# Matias_OBC-v_3_0.net
KiCad netlist of a schematic drawn in EAGLE
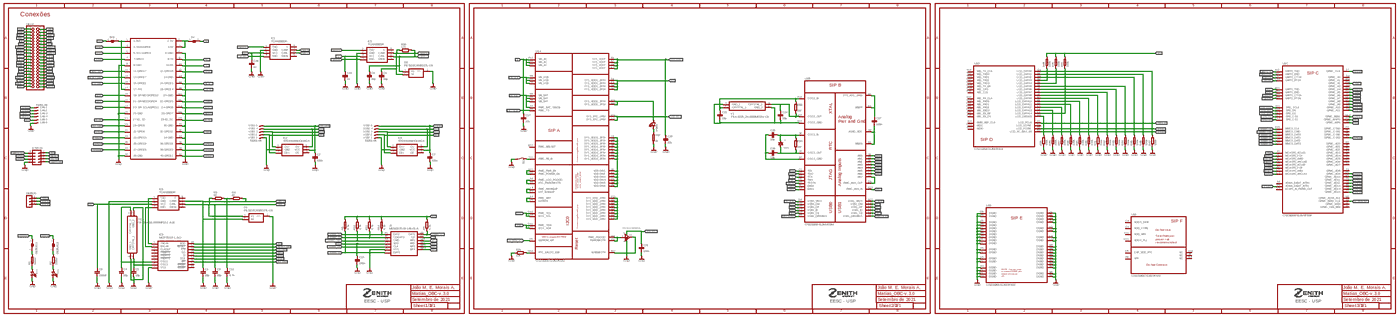
[diagram p0: schematic, sheet 1, overview]
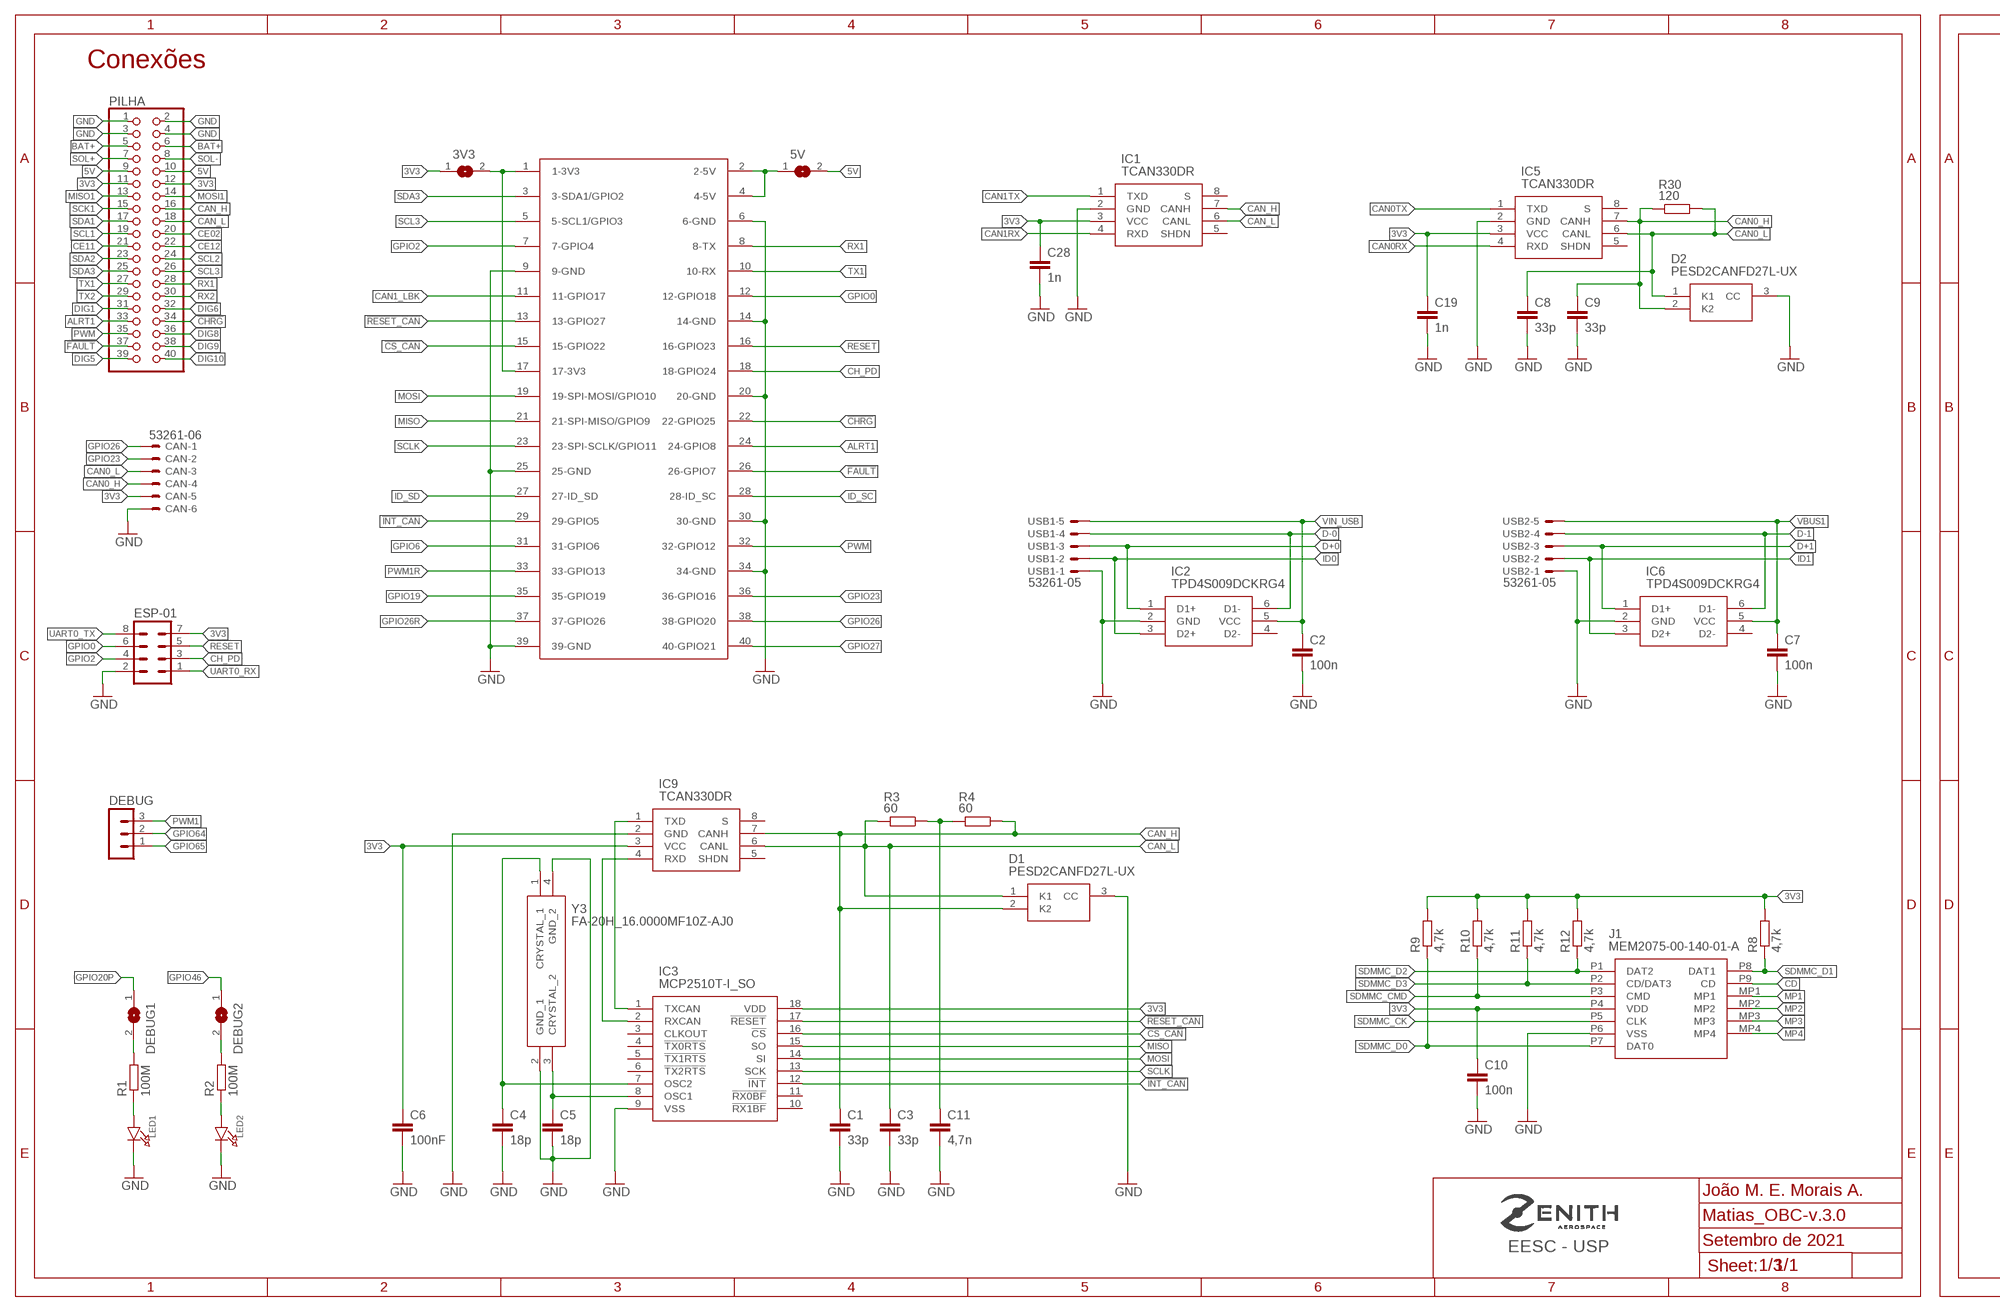
[diagram p1: schematic, sheet 1, part 1 of 4]
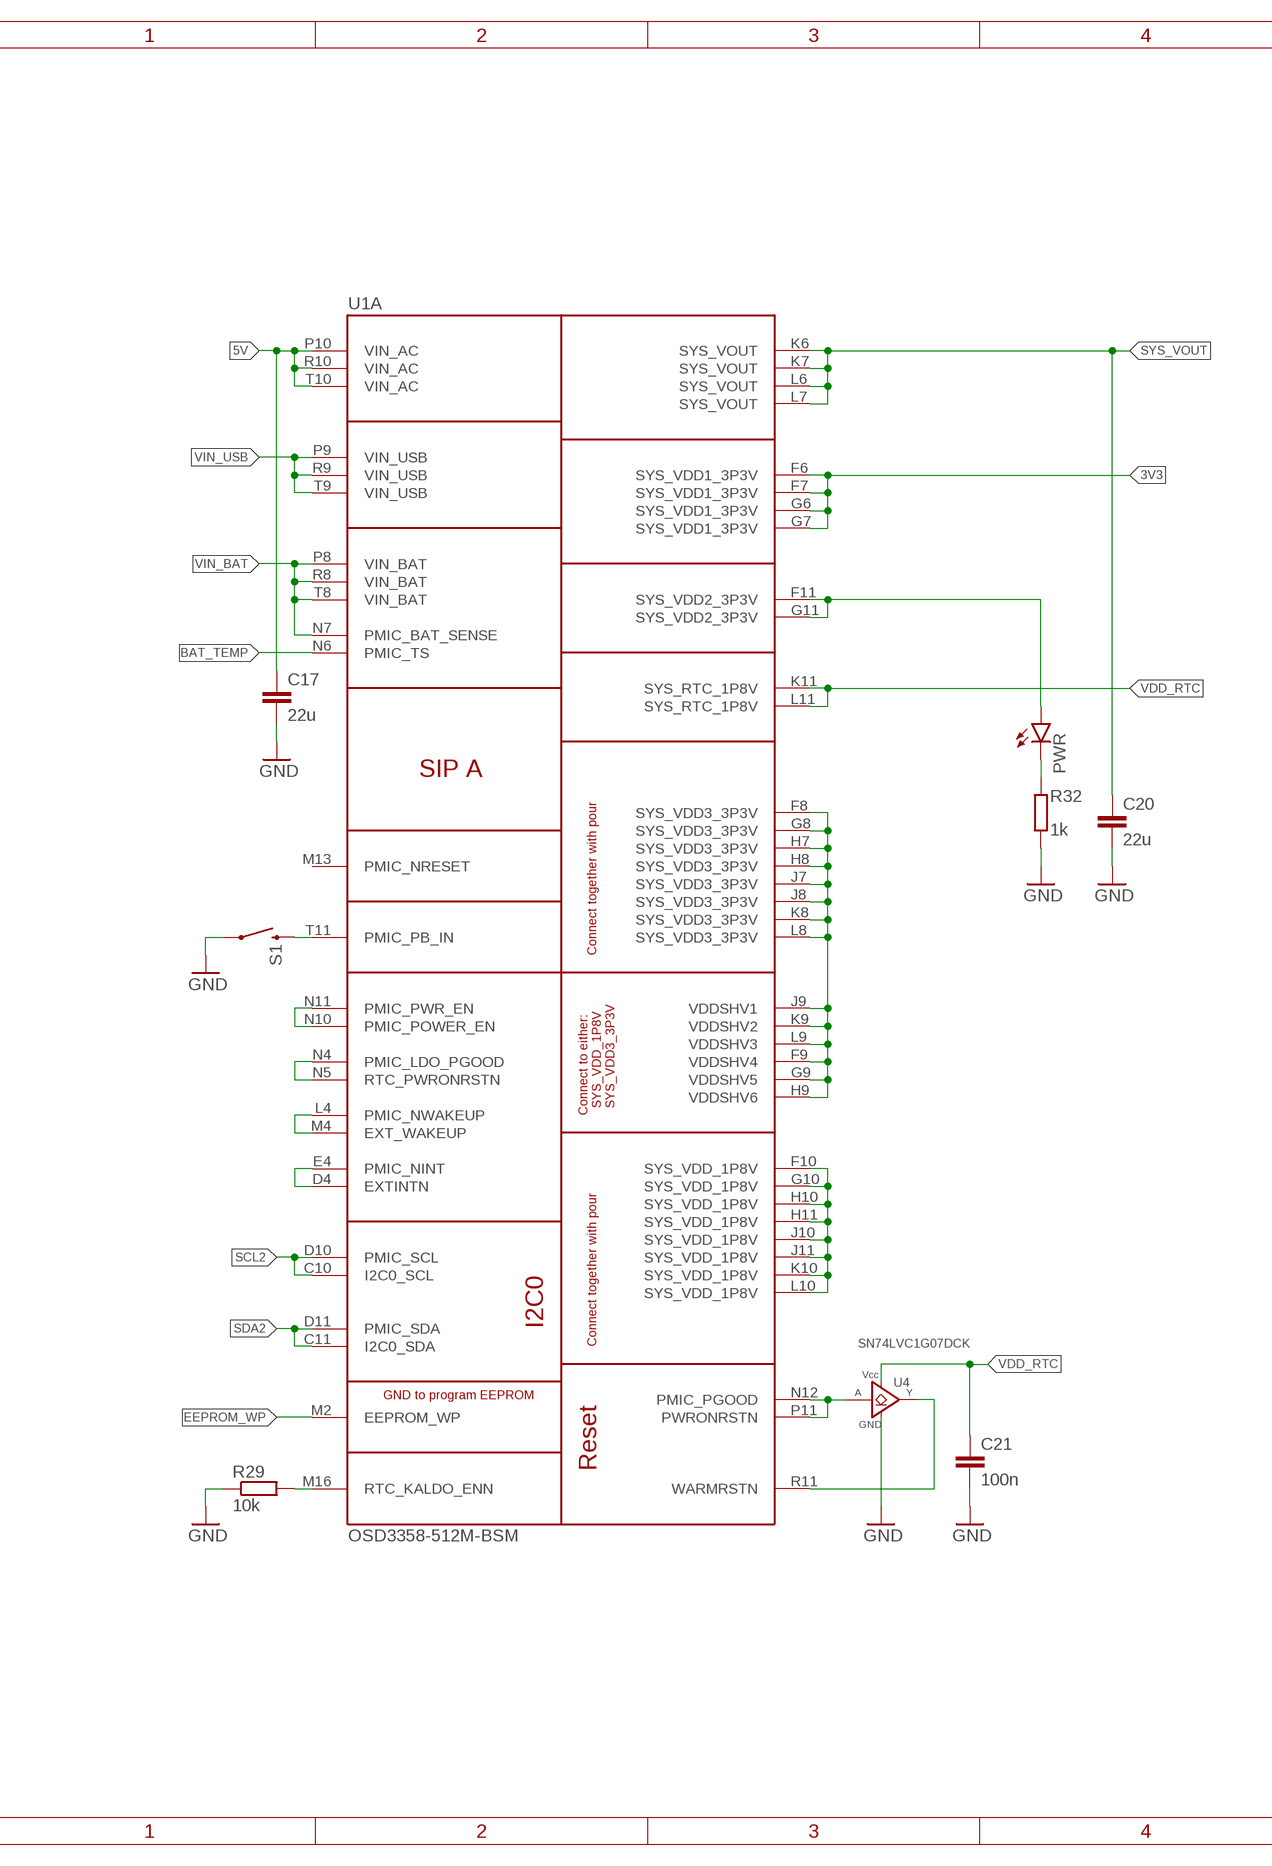
[diagram p2: schematic, sheet 1, part 2 of 4]
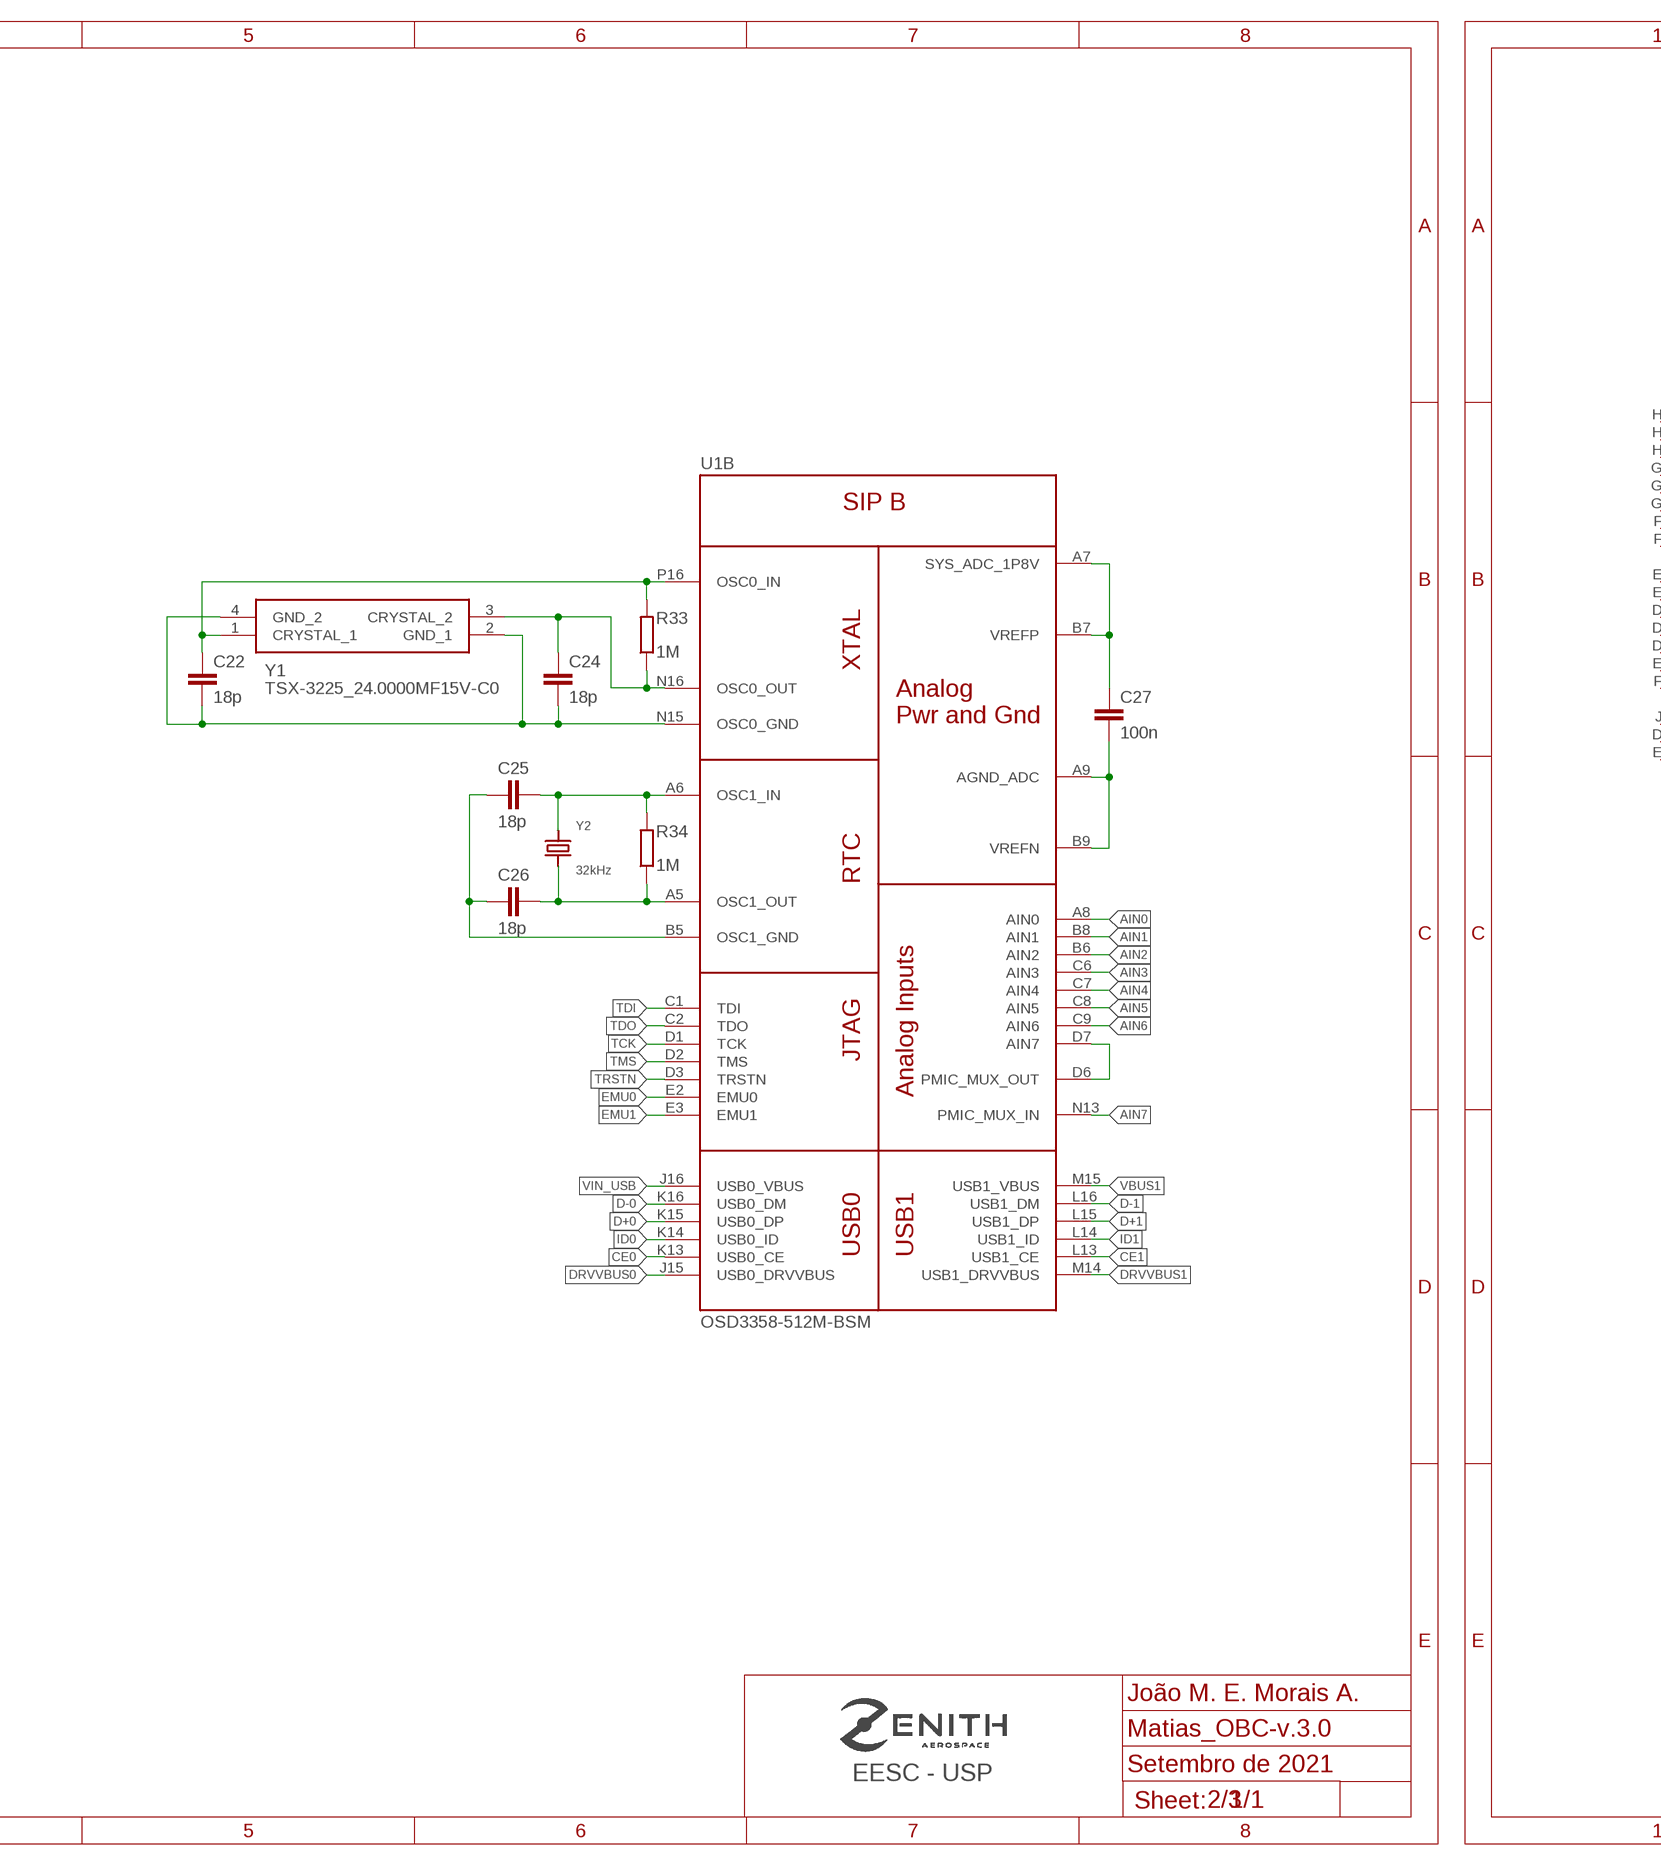
[diagram p3: schematic, sheet 1, part 3 of 4]
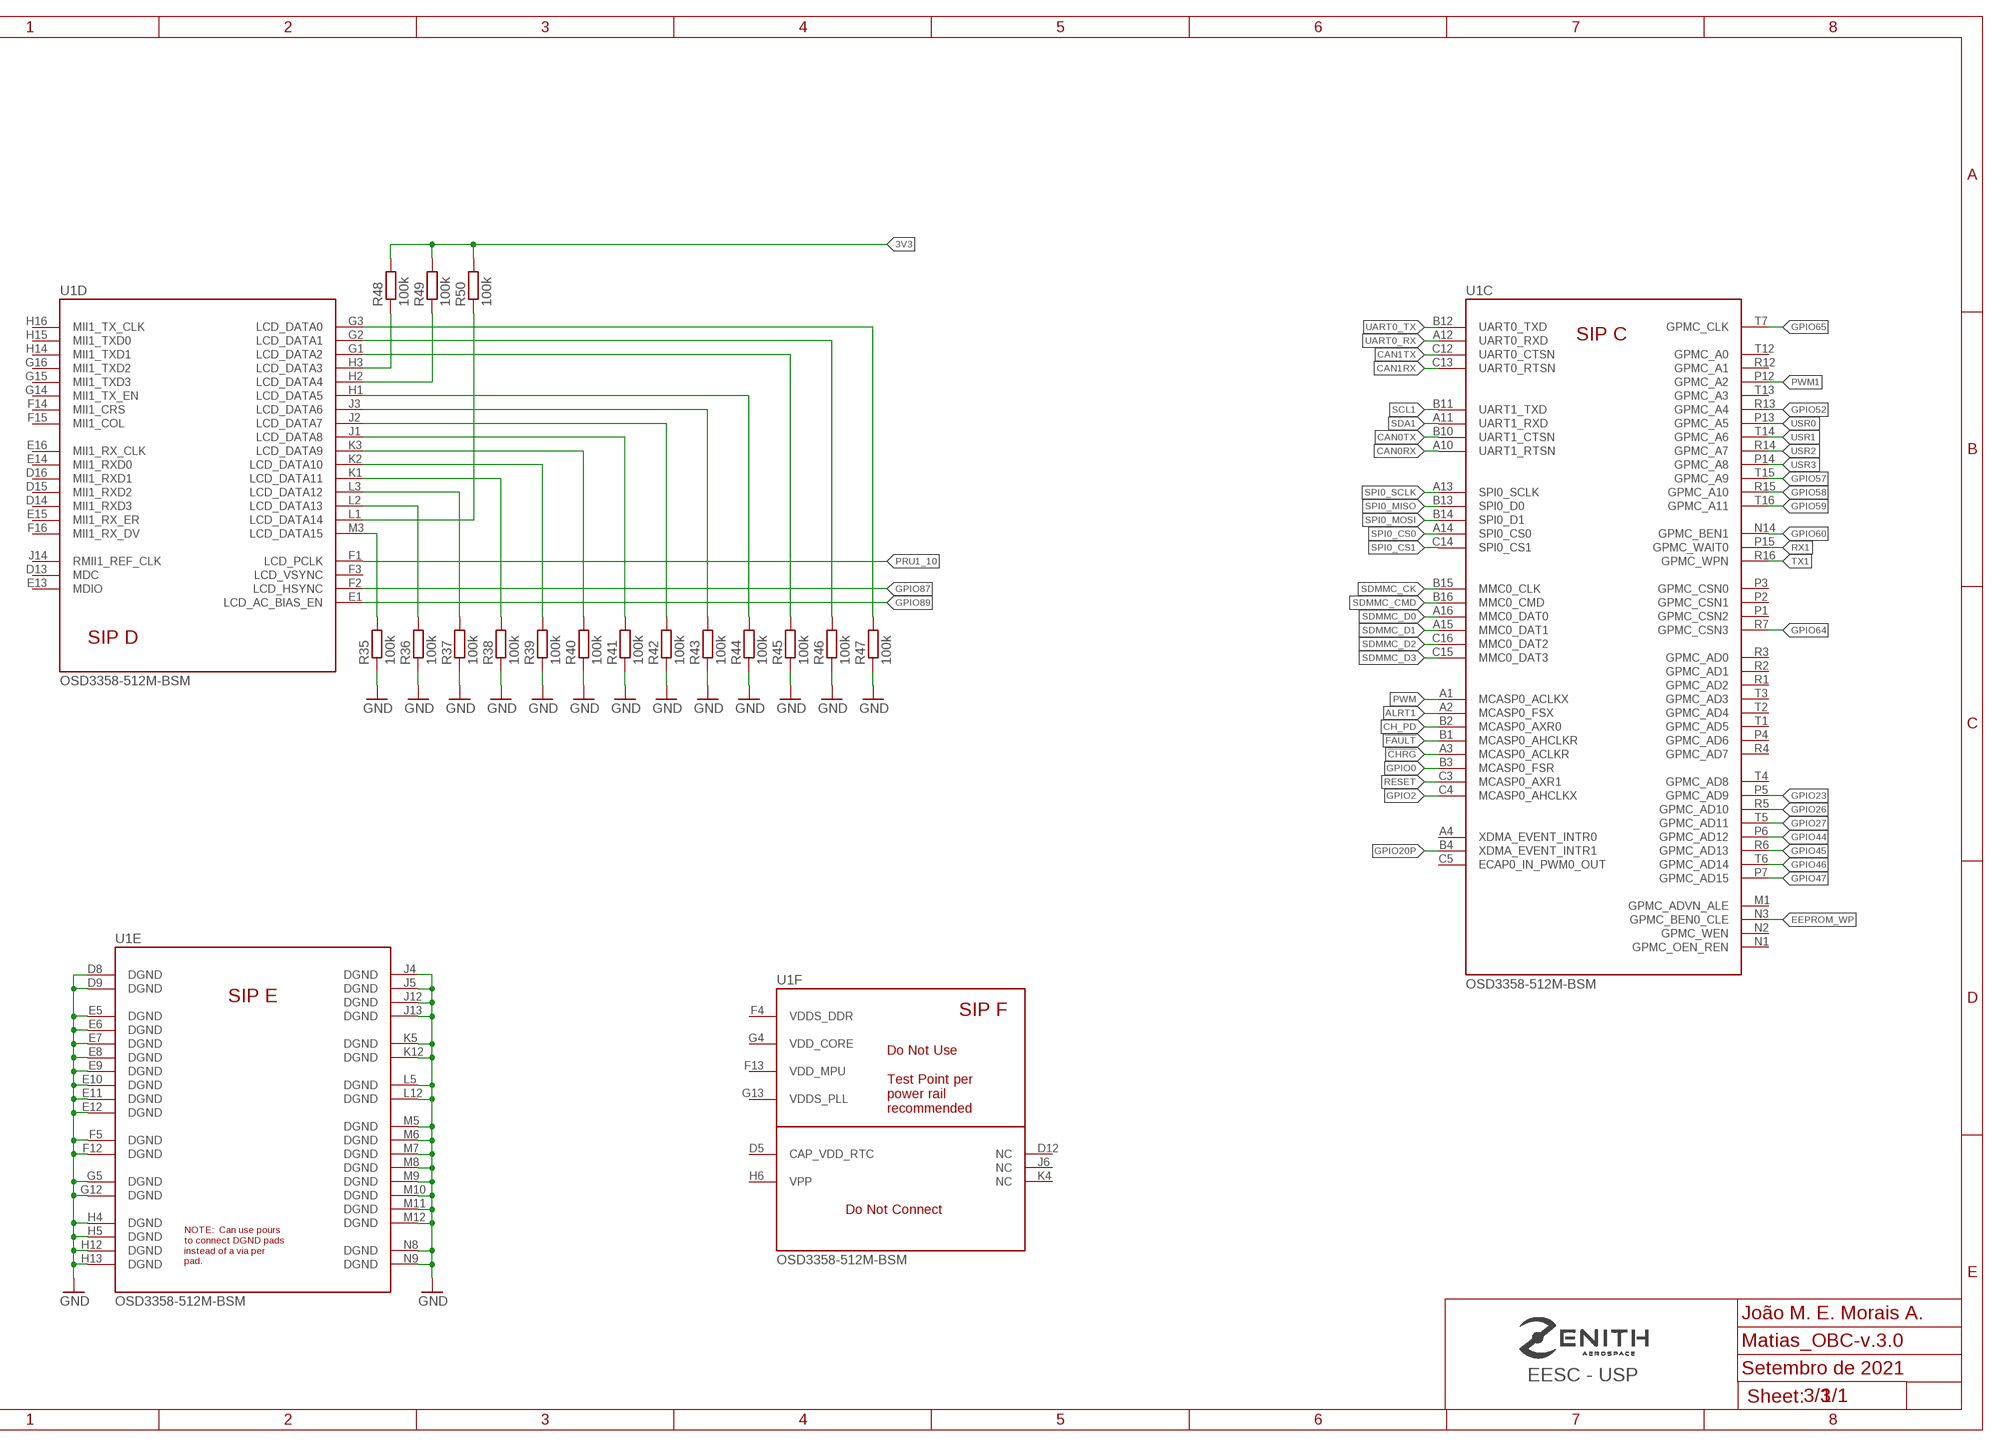
[diagram p4: schematic, sheet 1, part 4 of 4]

(export (version "E")
  (design (tool "Eeschema 10.0.6"))
  (components
    (comp (ref "3V3") (value "SJ") (footprint "eagle-import:SJ") (libsource (lib "eagle-import") (part "SJ")))
    (comp (ref "5V") (value "SJ") (footprint "eagle-import:SJ") (libsource (lib "eagle-import") (part "SJ")))
    (comp (ref "C1")
      (value "33p")
      (footprint "eagle-import:C0805")
      (libsource (lib "eagle-import") (part "C-EUC0805"))
    )
    (comp (ref "C2")
      (value "100n")
      (footprint "eagle-import:C0805")
      (libsource (lib "eagle-import") (part "C-EUC0805"))
    )
    (comp (ref "C3")
      (value "33p")
      (footprint "eagle-import:C0805")
      (libsource (lib "eagle-import") (part "C-EUC0805"))
    )
    (comp (ref "C4")
      (value "18p")
      (footprint "eagle-import:C0805")
      (libsource (lib "eagle-import") (part "C-EUC0805"))
    )
    (comp (ref "C5")
      (value "18p")
      (footprint "eagle-import:C0805")
      (libsource (lib "eagle-import") (part "C-EUC0805"))
    )
    (comp (ref "C6")
      (value "100nF")
      (footprint "eagle-import:C0805")
      (libsource (lib "eagle-import") (part "C-EUC0805"))
    )
    (comp (ref "C7")
      (value "100n")
      (footprint "eagle-import:C0805")
      (libsource (lib "eagle-import") (part "C-EUC0805"))
    )
    (comp (ref "C8")
      (value "33p")
      (footprint "eagle-import:C0805")
      (libsource (lib "eagle-import") (part "C-EUC0805"))
    )
    (comp (ref "C9")
      (value "33p")
      (footprint "eagle-import:C0805")
      (libsource (lib "eagle-import") (part "C-EUC0805"))
    )
    (comp (ref "C10")
      (value "100n")
      (footprint "eagle-import:C0805")
      (libsource (lib "eagle-import") (part "C-EUC0805"))
    )
    (comp (ref "C11")
      (value "4,7n")
      (footprint "eagle-import:C0805")
      (libsource (lib "eagle-import") (part "C-EUC0805"))
    )
    (comp (ref "C17")
      (value "22u")
      (footprint "eagle-import:C0805")
      (libsource (lib "eagle-import") (part "C-EUC0805"))
    )
    (comp (ref "C19")
      (value "1n")
      (footprint "eagle-import:C0805")
      (libsource (lib "eagle-import") (part "C-EUC0805"))
    )
    (comp (ref "C20")
      (value "22u")
      (footprint "eagle-import:C0805")
      (libsource (lib "eagle-import") (part "C-EUC0805"))
    )
    (comp (ref "C21")
      (value "100n")
      (footprint "eagle-import:C0805")
      (libsource (lib "eagle-import") (part "C-EUC0805"))
    )
    (comp (ref "C22")
      (value "18p")
      (footprint "eagle-import:C0805")
      (libsource (lib "eagle-import") (part "C-EUC0805"))
    )
    (comp (ref "C24")
      (value "18p")
      (footprint "eagle-import:C0805")
      (libsource (lib "eagle-import") (part "C-EUC0805"))
    )
    (comp (ref "C25")
      (value "18p")
      (footprint "eagle-import:C0805")
      (libsource (lib "eagle-import") (part "C-EUC0805"))
    )
    (comp (ref "C26")
      (value "18p")
      (footprint "eagle-import:C0805")
      (libsource (lib "eagle-import") (part "C-EUC0805"))
    )
    (comp (ref "C27")
      (value "100n")
      (footprint "eagle-import:C0805")
      (libsource (lib "eagle-import") (part "C-EUC0805"))
    )
    (comp (ref "C28")
      (value "1n")
      (footprint "eagle-import:C0805")
      (libsource (lib "eagle-import") (part "C-EUC0805"))
    )
    (comp (ref "CAN")
      (value "53261-06")
      (footprint "eagle-import:53261-06")
      (fields (field (name "MF") "MOLEX"))
      (libsource (lib "eagle-import") (part "53?-06261"))
    )
    (comp (ref "D1")
      (value "PESD2CANFD27L-UX")
      (footprint "eagle-import:SOT65P210X110-3N")
      (fields (field (name "MOUSER_PART_NUMBER") "771-PESD2CANFD27L-UX"))
      (libsource (lib "eagle-import") (part "PESD2CANFD27L-UX"))
    )
    (comp (ref "D2")
      (value "PESD2CANFD27L-UX")
      (footprint "eagle-import:SOT65P210X110-3N")
      (fields (field (name "MOUSER_PART_NUMBER") "771-PESD2CANFD27L-UX"))
      (libsource (lib "eagle-import") (part "PESD2CANFD27L-UX"))
    )
    (comp (ref "DEBUG")
      (value "MA03-1")
      (footprint "eagle-import:MA03-1")
      (libsource (lib "eagle-import") (part "MA03-1"))
    )
    (comp (ref "DEBUG1")
      (value "SOLDERJUMPERREFLOW_NOPASTE")
      (footprint "eagle-import:SOLDERJUMPER_REFLOW_NOPASTE")
      (libsource (lib "eagle-import") (part "SOLDERJUMPERREFLOW_NOPASTE"))
    )
    (comp (ref "DEBUG2")
      (value "SOLDERJUMPERREFLOW_NOPASTE")
      (footprint "eagle-import:SOLDERJUMPER_REFLOW_NOPASTE")
      (libsource (lib "eagle-import") (part "SOLDERJUMPERREFLOW_NOPASTE"))
    )
    (comp (ref "ESP-01")
      (value "MA04-2")
      (footprint "eagle-import:MA04-2")
      (libsource (lib "eagle-import") (part "MA04-2"))
    )
    (comp (ref "IC1")
      (value "TCAN330DR")
      (footprint "eagle-import:SOIC127P600X175-8N")
      (fields (field (name "MOUSER_PART_NUMBER") "595-TCAN330DR"))
      (libsource (lib "eagle-import") (part "TCAN330DR"))
    )
    (comp (ref "IC2")
      (value "TPD4S009DCKRG4")
      (footprint "eagle-import:SOT65P210X110-6N")
      (fields (field (name "MOUSER_PART_NUMBER") "595-TPD4S009DCKRG4"))
      (libsource (lib "eagle-import") (part "TPD4S009DCKRG4"))
    )
    (comp (ref "IC3")
      (value "MCP2510T-I_SO")
      (footprint "eagle-import:SOIC127P1030X265-18N")
      (fields
        (field (name "MANUFACTURER_PART_NUMBER") "MCP2510T-I/SO")
        (field (name "MOUSER_PART_NUMBER") "579-MCP2510T-I/SO")
      )
      (libsource (lib "eagle-import") (part "MCP2510T-I_SO"))
    )
    (comp (ref "IC5")
      (value "TCAN330DR")
      (footprint "eagle-import:SOIC127P600X175-8N")
      (fields (field (name "MOUSER_PART_NUMBER") "595-TCAN330DR"))
      (libsource (lib "eagle-import") (part "TCAN330DR"))
    )
    (comp (ref "IC6")
      (value "TPD4S009DCKRG4")
      (footprint "eagle-import:SOT65P210X110-6N")
      (fields (field (name "MOUSER_PART_NUMBER") "595-TPD4S009DCKRG4"))
      (libsource (lib "eagle-import") (part "TPD4S009DCKRG4"))
    )
    (comp (ref "IC9")
      (value "TCAN330DR")
      (footprint "eagle-import:SOIC127P600X175-8N")
      (fields (field (name "MOUSER_PART_NUMBER") "595-TCAN330DR"))
      (libsource (lib "eagle-import") (part "TCAN330DR"))
    )
    (comp (ref "J1")
      (value "MEM2075-00-140-01-A")
      (footprint "eagle-import:MEM20750014001A")
      (fields (field (name "MOUSER_PART_NUMBER") "640-MEM20750014001A"))
      (libsource (lib "eagle-import") (part "MEM2075-00-140-01-A"))
    )
    (comp (ref "LED1")
      (value "LED1206")
      (footprint "eagle-import:CHIPLED_1206")
      (libsource (lib "eagle-import") (part "LED1206"))
    )
    (comp (ref "LED2")
      (value "LED1206")
      (footprint "eagle-import:CHIPLED_1206")
      (libsource (lib "eagle-import") (part "LED1206"))
    )
    (comp (ref "PILHA")
      (value "PINHD-2X20")
      (footprint "eagle-import:2X20")
      (libsource (lib "eagle-import") (part "PINHD-2X20"))
    )
    (comp (ref "PWR")
      (value "LEDCHIP-LED0805")
      (footprint "eagle-import:CHIP-LED0805")
      (libsource (lib "eagle-import") (part "LEDCHIP-LED0805"))
    )
    (comp (ref "R1")
      (value "100M")
      (footprint "eagle-import:R0805")
      (libsource (lib "eagle-import") (part "R-EU_R0805"))
    )
    (comp (ref "R2")
      (value "100M")
      (footprint "eagle-import:R0805")
      (libsource (lib "eagle-import") (part "R-EU_R0805"))
    )
    (comp (ref "R3")
      (value "60")
      (footprint "eagle-import:R0805")
      (libsource (lib "eagle-import") (part "R-EU_R0805"))
    )
    (comp (ref "R4")
      (value "60")
      (footprint "eagle-import:R0805")
      (libsource (lib "eagle-import") (part "R-EU_R0805"))
    )
    (comp (ref "R8")
      (value "4,7k")
      (footprint "eagle-import:R0805")
      (libsource (lib "eagle-import") (part "R-EU_R0805"))
    )
    (comp (ref "R9")
      (value "4,7k")
      (footprint "eagle-import:R0805")
      (libsource (lib "eagle-import") (part "R-EU_R0805"))
    )
    (comp (ref "R10")
      (value "4,7k")
      (footprint "eagle-import:R0805")
      (libsource (lib "eagle-import") (part "R-EU_R0805"))
    )
    (comp (ref "R11")
      (value "4,7k")
      (footprint "eagle-import:R0805")
      (libsource (lib "eagle-import") (part "R-EU_R0805"))
    )
    (comp (ref "R12")
      (value "4,7k")
      (footprint "eagle-import:R0805")
      (libsource (lib "eagle-import") (part "R-EU_R0805"))
    )
    (comp (ref "R29")
      (value "10k")
      (footprint "eagle-import:R0805")
      (libsource (lib "eagle-import") (part "R-EU_R0805"))
    )
    (comp (ref "R30")
      (value "120")
      (footprint "eagle-import:R0805")
      (libsource (lib "eagle-import") (part "R-EU_R0805"))
    )
    (comp (ref "R32")
      (value "1k")
      (footprint "eagle-import:R0805")
      (libsource (lib "eagle-import") (part "R-EU_R0805"))
    )
    (comp (ref "R33")
      (value "1M")
      (footprint "eagle-import:R0805")
      (libsource (lib "eagle-import") (part "R-EU_R0805"))
    )
    (comp (ref "R34")
      (value "1M")
      (footprint "eagle-import:R0805")
      (libsource (lib "eagle-import") (part "R-EU_R0805"))
    )
    (comp (ref "R35")
      (value "100k")
      (footprint "eagle-import:R0805")
      (libsource (lib "eagle-import") (part "R-EU_R0805"))
    )
    (comp (ref "R36")
      (value "100k")
      (footprint "eagle-import:R0805")
      (libsource (lib "eagle-import") (part "R-EU_R0805"))
    )
    (comp (ref "R37")
      (value "100k")
      (footprint "eagle-import:R0805")
      (libsource (lib "eagle-import") (part "R-EU_R0805"))
    )
    (comp (ref "R38")
      (value "100k")
      (footprint "eagle-import:R0805")
      (libsource (lib "eagle-import") (part "R-EU_R0805"))
    )
    (comp (ref "R39")
      (value "100k")
      (footprint "eagle-import:R0805")
      (libsource (lib "eagle-import") (part "R-EU_R0805"))
    )
    (comp (ref "R40")
      (value "100k")
      (footprint "eagle-import:R0805")
      (libsource (lib "eagle-import") (part "R-EU_R0805"))
    )
    (comp (ref "R41")
      (value "100k")
      (footprint "eagle-import:R0805")
      (libsource (lib "eagle-import") (part "R-EU_R0805"))
    )
    (comp (ref "R42")
      (value "100k")
      (footprint "eagle-import:R0805")
      (libsource (lib "eagle-import") (part "R-EU_R0805"))
    )
    (comp (ref "R43")
      (value "100k")
      (footprint "eagle-import:R0805")
      (libsource (lib "eagle-import") (part "R-EU_R0805"))
    )
    (comp (ref "R44")
      (value "100k")
      (footprint "eagle-import:R0805")
      (libsource (lib "eagle-import") (part "R-EU_R0805"))
    )
    (comp (ref "R45")
      (value "100k")
      (footprint "eagle-import:R0805")
      (libsource (lib "eagle-import") (part "R-EU_R0805"))
    )
    (comp (ref "R46")
      (value "100k")
      (footprint "eagle-import:R0805")
      (libsource (lib "eagle-import") (part "R-EU_R0805"))
    )
    (comp (ref "R47")
      (value "100k")
      (footprint "eagle-import:R0805")
      (libsource (lib "eagle-import") (part "R-EU_R0805"))
    )
    (comp (ref "R48")
      (value "100k")
      (footprint "eagle-import:R0805")
      (libsource (lib "eagle-import") (part "R-EU_R0805"))
    )
    (comp (ref "R49")
      (value "100k")
      (footprint "eagle-import:R0805")
      (libsource (lib "eagle-import") (part "R-EU_R0805"))
    )
    (comp (ref "R50")
      (value "100k")
      (footprint "eagle-import:R0805")
      (libsource (lib "eagle-import") (part "R-EU_R0805"))
    )
    (comp (ref "S1")
      (value "MOMENTARY-SWITCH-SPST-SMD-6.0X3.5MM")
      (footprint "eagle-import:TACTILE_SWITCH_SMD_6.0X3.5MM")
      (libsource (lib "eagle-import") (part "MOMENTARY-SWITCH-SPST-SMD-6.0X3.5MM"))
    )
    (comp (ref "U1")
      (value "OSD3358-512M-BSM")
      (footprint "eagle-import:OSD335X-BGA-256")
      (fields (field (name "MFR") "Octavo Systems"))
      (libsource (lib "eagle-import") (part "OSD3358-512M-BSM"))
    )
    (comp (ref "U2")
      (value "RASPBERRY-PI+PIZERO")
      (footprint "eagle-import:RASPBERRY-PI-ZERO")
      (libsource (lib "eagle-import") (part "RASPBERRY-PI+PIZERO"))
    )
    (comp (ref "U4")
      (value "SN74LVC1G07DCK")
      (footprint "eagle-import:SC70(TI-DCK)")
      (libsource (lib "eagle-import") (part "SN74LVC1G07DCK"))
    )
    (comp (ref "USB1")
      (value "53261-05")
      (footprint "eagle-import:53261-05")
      (fields (field (name "MF") "MOLEX"))
      (libsource (lib "eagle-import") (part "53?-05261"))
    )
    (comp (ref "USB2")
      (value "53261-05")
      (footprint "eagle-import:53261-05")
      (fields (field (name "MF") "MOLEX"))
      (libsource (lib "eagle-import") (part "53?-05261"))
    )
    (comp (ref "Y1")
      (value "TSX-3225_24.0000MF15V-C0")
      (footprint "eagle-import:TSX3225240000MF15VC0")
      (fields
        (field (name "MANUFACTURER_PART_NUMBER") "TSX-3225 24.0000MF15V-C0")
        (field (name "MOUSER_PART_NUMBER") "732-22524MF15V-C")
      )
      (libsource (lib "eagle-import") (part "TSX-3225_24.0000MF15V-C0"))
    )
    (comp (ref "Y2")
      (value "32kHz")
      (footprint "eagle-import:CRYSTAL_8X3.8")
      (libsource (lib "eagle-import") (part "CRYSTAL8X3.8SMT"))
    )
    (comp (ref "Y3")
      (value "FA-20H_16.0000MF10Z-AJ0")
      (footprint "eagle-import:FA20H160000MF12ZAC3")
      (fields
        (field (name "MANUFACTURER_PART_NUMBER") "FA-20H 16.0000MF10Z-AJ0")
        (field (name "MOUSER_PART_NUMBER") "732-FA-20H16MF10ZAJ0")
      )
      (libsource (lib "eagle-import") (part "FA-20H_16.0000MF10Z-AJ0"))
    )
  )
  (nets
    (net (code "1") (name "/~{CHRG}") (class "Default")
      (node (ref "PILHA") (pin "34") (pinfunction "34_34") (pintype "passive"))
      (node (ref "U1") (pin "A3") (pinfunction "MCASP0_ACLKR_A3") (pintype "bidirectional"))
      (node (ref "U2") (pin "22") (pinfunction "22-GPIO25_22") (pintype "bidirectional"))
    )
    (net (code "2") (name "/~{CS_CAN}") (class "Default")
      (node (ref "IC3") (pin "16") (pinfunction "~{CS}_16") (pintype "input"))
      (node (ref "U2") (pin "15") (pinfunction "15-GPIO22_15") (pintype "bidirectional"))
    )
    (net (code "3") (name "/~{FAULT}") (class "Default")
      (node (ref "PILHA") (pin "37") (pinfunction "37_37") (pintype "passive"))
      (node (ref "U1") (pin "B1") (pinfunction "MCASP0_AHCLKR_B1") (pintype "bidirectional"))
      (node (ref "U2") (pin "26") (pinfunction "26-GPIO7_26") (pintype "bidirectional"))
    )
    (net (code "4") (name "/~{INT_CAN}") (class "Default")
      (node (ref "IC3") (pin "12") (pinfunction "~{INT}_12") (pintype "input"))
      (node (ref "U2") (pin "29") (pinfunction "29-GPIO5_29") (pintype "bidirectional"))
    )
    (net (code "5") (name "/~{RESET_CAN}") (class "Default")
      (node (ref "IC3") (pin "17") (pinfunction "~{RESET}_17") (pintype "bidirectional"))
      (node (ref "U2") (pin "13") (pinfunction "13-GPIO27_13") (pintype "bidirectional"))
    )
    (net (code "6") (name "3V3") (class "Default")
      (node (ref "3V3") (pin "1") (pinfunction "1_1") (pintype "passive"))
      (node (ref "C10") (pin "1") (pinfunction "1_1") (pintype "passive"))
      (node (ref "C19") (pin "1") (pinfunction "1_1") (pintype "passive"))
      (node (ref "C28") (pin "1") (pinfunction "1_1") (pintype "passive"))
      (node (ref "C6") (pin "1") (pinfunction "1_1") (pintype "passive"))
      (node (ref "CAN") (pin "5") (pinfunction "S_5") (pintype "passive"))
      (node (ref "ESP-01") (pin "7") (pinfunction "7_7") (pintype "passive"))
      (node (ref "IC1") (pin "3") (pinfunction "VCC_3") (pintype "bidirectional"))
      (node (ref "IC3") (pin "18") (pinfunction "VDD_18") (pintype "power_in"))
      (node (ref "IC5") (pin "3") (pinfunction "VCC_3") (pintype "bidirectional"))
      (node (ref "IC9") (pin "3") (pinfunction "VCC_3") (pintype "bidirectional"))
      (node (ref "J1") (pin "P4") (pinfunction "VDD_P4") (pintype "bidirectional"))
      (node (ref "PILHA") (pin "11") (pinfunction "11_11") (pintype "passive"))
      (node (ref "PILHA") (pin "12") (pinfunction "12_12") (pintype "passive"))
      (node (ref "R10") (pin "2") (pinfunction "2_2") (pintype "passive"))
      (node (ref "R11") (pin "2") (pinfunction "2_2") (pintype "passive"))
      (node (ref "R12") (pin "2") (pinfunction "2_2") (pintype "passive"))
      (node (ref "R48") (pin "2") (pinfunction "2_2") (pintype "passive"))
      (node (ref "R49") (pin "2") (pinfunction "2_2") (pintype "passive"))
      (node (ref "R50") (pin "2") (pinfunction "2_2") (pintype "passive"))
      (node (ref "R8") (pin "2") (pinfunction "2_2") (pintype "passive"))
      (node (ref "R9") (pin "2") (pinfunction "2_2") (pintype "passive"))
      (node (ref "U1") (pin "F6") (pinfunction "SYS_VDD1_3P3V_F6") (pintype "power_in"))
      (node (ref "U1") (pin "F7") (pinfunction "SYS_VDD1_3P3V_F7") (pintype "power_in"))
      (node (ref "U1") (pin "G6") (pinfunction "SYS_VDD1_3P3V_G6") (pintype "power_in"))
      (node (ref "U1") (pin "G7") (pinfunction "SYS_VDD1_3P3V_G7") (pintype "power_in"))
    )
    (net (code "7") (name "5V") (class "Default")
      (node (ref "5V") (pin "2") (pinfunction "2_2") (pintype "passive"))
      (node (ref "C17") (pin "1") (pinfunction "1_1") (pintype "passive"))
      (node (ref "PILHA") (pin "10") (pinfunction "10_10") (pintype "passive"))
      (node (ref "PILHA") (pin "9") (pinfunction "9_9") (pintype "passive"))
      (node (ref "U1") (pin "P10") (pinfunction "VIN_AC_P10") (pintype "power_in"))
      (node (ref "U1") (pin "R10") (pinfunction "VIN_AC_R10") (pintype "power_in"))
      (node (ref "U1") (pin "T10") (pinfunction "VIN_AC_T10") (pintype "power_in"))
    )
    (net (code "8") (name "AIN0") (class "Default")
      (node (ref "U1") (pin "A8") (pinfunction "AIN0_A8") (pintype "bidirectional"))
    )
    (net (code "9") (name "AIN1") (class "Default")
      (node (ref "U1") (pin "B8") (pinfunction "AIN1_B8") (pintype "bidirectional"))
    )
    (net (code "10") (name "AIN2") (class "Default")
      (node (ref "U1") (pin "B6") (pinfunction "AIN2_B6") (pintype "bidirectional"))
    )
    (net (code "11") (name "AIN3") (class "Default")
      (node (ref "U1") (pin "C6") (pinfunction "AIN3_C6") (pintype "bidirectional"))
    )
    (net (code "12") (name "AIN4") (class "Default")
      (node (ref "U1") (pin "C7") (pinfunction "AIN4_C7") (pintype "bidirectional"))
    )
    (net (code "13") (name "AIN5") (class "Default")
      (node (ref "U1") (pin "C8") (pinfunction "AIN5_C8") (pintype "bidirectional"))
    )
    (net (code "14") (name "AIN6") (class "Default")
      (node (ref "U1") (pin "C9") (pinfunction "AIN6_C9") (pintype "bidirectional"))
    )
    (net (code "15") (name "AIN7") (class "Default")
      (node (ref "U1") (pin "N13") (pinfunction "PMIC_MUX_IN_N13") (pintype "bidirectional"))
    )
    (net (code "16") (name "ALRT1") (class "Default")
      (node (ref "PILHA") (pin "33") (pinfunction "33_33") (pintype "passive"))
      (node (ref "U1") (pin "A2") (pinfunction "MCASP0_FSX_A2") (pintype "bidirectional"))
      (node (ref "U2") (pin "24") (pinfunction "24-GPIO8_24") (pintype "bidirectional"))
    )
    (net (code "17") (name "BAT+") (class "Default")
      (node (ref "PILHA") (pin "5") (pinfunction "5_5") (pintype "passive"))
      (node (ref "PILHA") (pin "6") (pinfunction "6_6") (pintype "passive"))
    )
    (net (code "18") (name "BAT_TEMP") (class "Default")
      (node (ref "U1") (pin "N6") (pinfunction "PMIC_TS_N6") (pintype "bidirectional"))
    )
    (net (code "19") (name "CAN0RX") (class "Default")
      (node (ref "IC5") (pin "4") (pinfunction "RXD_4") (pintype "bidirectional"))
      (node (ref "U1") (pin "A10") (pinfunction "UART1_RTSN_A10") (pintype "bidirectional"))
    )
    (net (code "20") (name "CAN0TX") (class "Default")
      (node (ref "IC5") (pin "1") (pinfunction "TXD_1") (pintype "bidirectional"))
      (node (ref "U1") (pin "B10") (pinfunction "UART1_CTSN_B10") (pintype "bidirectional"))
    )
    (net (code "21") (name "CAN0_H") (class "Default")
      (node (ref "C9") (pin "1") (pinfunction "1_1") (pintype "passive"))
      (node (ref "CAN") (pin "4") (pinfunction "S_4") (pintype "passive"))
      (node (ref "D2") (pin "2") (pinfunction "K2_2") (pintype "bidirectional"))
      (node (ref "IC5") (pin "7") (pinfunction "CANH_7") (pintype "bidirectional"))
      (node (ref "R30") (pin "1") (pinfunction "1_1") (pintype "passive"))
    )
    (net (code "22") (name "CAN0_L") (class "Default")
      (node (ref "C8") (pin "1") (pinfunction "1_1") (pintype "passive"))
      (node (ref "CAN") (pin "3") (pinfunction "S_3") (pintype "passive"))
      (node (ref "D2") (pin "1") (pinfunction "K1_1") (pintype "bidirectional"))
      (node (ref "IC5") (pin "6") (pinfunction "CANL_6") (pintype "bidirectional"))
      (node (ref "R30") (pin "2") (pinfunction "2_2") (pintype "passive"))
    )
    (net (code "23") (name "CAN1RX") (class "Default")
      (node (ref "IC1") (pin "4") (pinfunction "RXD_4") (pintype "bidirectional"))
      (node (ref "U1") (pin "C13") (pinfunction "UART0_RTSN_C13") (pintype "bidirectional"))
    )
    (net (code "24") (name "CAN1TX") (class "Default")
      (node (ref "IC1") (pin "1") (pinfunction "TXD_1") (pintype "bidirectional"))
      (node (ref "U1") (pin "C12") (pinfunction "UART0_CTSN_C12") (pintype "bidirectional"))
    )
    (net (code "25") (name "CAN1_LBK") (class "Default")
      (node (ref "U2") (pin "11") (pinfunction "11-GPIO17_11") (pintype "bidirectional"))
    )
    (net (code "26") (name "CAN_H") (class "Default")
      (node (ref "C1") (pin "1") (pinfunction "1_1") (pintype "passive"))
      (node (ref "D1") (pin "2") (pinfunction "K2_2") (pintype "bidirectional"))
      (node (ref "IC1") (pin "7") (pinfunction "CANH_7") (pintype "bidirectional"))
      (node (ref "IC9") (pin "7") (pinfunction "CANH_7") (pintype "bidirectional"))
      (node (ref "PILHA") (pin "16") (pinfunction "16_16") (pintype "passive"))
      (node (ref "R4") (pin "1") (pinfunction "1_1") (pintype "passive"))
    )
    (net (code "27") (name "CAN_L") (class "Default")
      (node (ref "C3") (pin "1") (pinfunction "1_1") (pintype "passive"))
      (node (ref "D1") (pin "1") (pinfunction "K1_1") (pintype "bidirectional"))
      (node (ref "IC1") (pin "6") (pinfunction "CANL_6") (pintype "bidirectional"))
      (node (ref "IC9") (pin "6") (pinfunction "CANL_6") (pintype "bidirectional"))
      (node (ref "PILHA") (pin "18") (pinfunction "18_18") (pintype "passive"))
      (node (ref "R3") (pin "2") (pinfunction "2_2") (pintype "passive"))
    )
    (net (code "28") (name "CD") (class "Default")
      (node (ref "J1") (pin "P9") (pinfunction "CD_P9") (pintype "bidirectional"))
    )
    (net (code "29") (name "CE0") (class "Default")
      (node (ref "U1") (pin "K13") (pinfunction "USB0_CE_K13") (pintype "bidirectional"))
    )
    (net (code "30") (name "CE1") (class "Default")
      (node (ref "U1") (pin "L13") (pinfunction "USB1_CE_L13") (pintype "bidirectional"))
    )
    (net (code "31") (name "CE02") (class "Default")
      (node (ref "PILHA") (pin "20") (pinfunction "20_20") (pintype "passive"))
    )
    (net (code "32") (name "CE11") (class "Default")
      (node (ref "PILHA") (pin "21") (pinfunction "21_21") (pintype "passive"))
    )
    (net (code "33") (name "CE12") (class "Default")
      (node (ref "PILHA") (pin "22") (pinfunction "22_22") (pintype "passive"))
    )
    (net (code "34") (name "CH_PD") (class "Default")
      (node (ref "ESP-01") (pin "3") (pinfunction "3_3") (pintype "passive"))
      (node (ref "U1") (pin "B2") (pinfunction "MCASP0_AXR0_B2") (pintype "bidirectional"))
      (node (ref "U2") (pin "18") (pinfunction "18-GPIO24_18") (pintype "bidirectional"))
    )
    (net (code "35") (name "D+0") (class "Default")
      (node (ref "IC2") (pin "1") (pinfunction "D1+_1") (pintype "bidirectional"))
      (node (ref "U1") (pin "K15") (pinfunction "USB0_DP_K15") (pintype "bidirectional"))
      (node (ref "USB1") (pin "3") (pinfunction "S_3") (pintype "passive"))
    )
    (net (code "36") (name "D+1") (class "Default")
      (node (ref "IC6") (pin "1") (pinfunction "D1+_1") (pintype "bidirectional"))
      (node (ref "U1") (pin "L15") (pinfunction "USB1_DP_L15") (pintype "bidirectional"))
      (node (ref "USB2") (pin "3") (pinfunction "S_3") (pintype "passive"))
    )
    (net (code "37") (name "D-0") (class "Default")
      (node (ref "IC2") (pin "6") (pinfunction "D1-_6") (pintype "bidirectional"))
      (node (ref "U1") (pin "K16") (pinfunction "USB0_DM_K16") (pintype "bidirectional"))
      (node (ref "USB1") (pin "4") (pinfunction "S_4") (pintype "passive"))
    )
    (net (code "38") (name "D-1") (class "Default")
      (node (ref "IC6") (pin "6") (pinfunction "D1-_6") (pintype "bidirectional"))
      (node (ref "U1") (pin "L16") (pinfunction "USB1_DM_L16") (pintype "bidirectional"))
      (node (ref "USB2") (pin "4") (pinfunction "S_4") (pintype "passive"))
    )
    (net (code "39") (name "DIG1") (class "Default")
      (node (ref "PILHA") (pin "31") (pinfunction "31_31") (pintype "passive"))
    )
    (net (code "40") (name "DIG5") (class "Default")
      (node (ref "PILHA") (pin "39") (pinfunction "39_39") (pintype "passive"))
    )
    (net (code "41") (name "DIG6") (class "Default")
      (node (ref "PILHA") (pin "32") (pinfunction "32_32") (pintype "passive"))
    )
    (net (code "42") (name "DIG8") (class "Default")
      (node (ref "PILHA") (pin "36") (pinfunction "36_36") (pintype "passive"))
    )
    (net (code "43") (name "DIG9") (class "Default")
      (node (ref "PILHA") (pin "38") (pinfunction "38_38") (pintype "passive"))
    )
    (net (code "44") (name "DIG10") (class "Default")
      (node (ref "PILHA") (pin "40") (pinfunction "40_40") (pintype "passive"))
    )
    (net (code "45") (name "DRVVBUS0") (class "Default")
      (node (ref "U1") (pin "J15") (pinfunction "USB0_DRVVBUS_J15") (pintype "bidirectional"))
    )
    (net (code "46") (name "DRVVBUS1") (class "Default")
      (node (ref "U1") (pin "M14") (pinfunction "USB1_DRVVBUS_M14") (pintype "bidirectional"))
    )
    (net (code "47") (name "EEPROM_WP") (class "Default")
      (node (ref "U1") (pin "M2") (pinfunction "EEPROM_WP_M2") (pintype "bidirectional"))
      (node (ref "U1") (pin "N3") (pinfunction "GPMC_BEN0_CLE_N3") (pintype "bidirectional"))
    )
    (net (code "48") (name "EMU0") (class "Default")
      (node (ref "U1") (pin "E2") (pinfunction "EMU0_E2") (pintype "bidirectional"))
    )
    (net (code "49") (name "EMU1") (class "Default")
      (node (ref "U1") (pin "E3") (pinfunction "EMU1_E3") (pintype "bidirectional"))
    )
    (net (code "50") (name "GND") (class "Default")
      (node (ref "C1") (pin "2") (pinfunction "2_2") (pintype "passive"))
      (node (ref "C10") (pin "2") (pinfunction "2_2") (pintype "passive"))
      (node (ref "C11") (pin "2") (pinfunction "2_2") (pintype "passive"))
      (node (ref "C17") (pin "2") (pinfunction "2_2") (pintype "passive"))
      (node (ref "C19") (pin "2") (pinfunction "2_2") (pintype "passive"))
      (node (ref "C2") (pin "2") (pinfunction "2_2") (pintype "passive"))
      (node (ref "C20") (pin "2") (pinfunction "2_2") (pintype "passive"))
      (node (ref "C21") (pin "2") (pinfunction "2_2") (pintype "passive"))
      (node (ref "C28") (pin "2") (pinfunction "2_2") (pintype "passive"))
      (node (ref "C3") (pin "2") (pinfunction "2_2") (pintype "passive"))
      (node (ref "C4") (pin "2") (pinfunction "2_2") (pintype "passive"))
      (node (ref "C5") (pin "2") (pinfunction "2_2") (pintype "passive"))
      (node (ref "C6") (pin "2") (pinfunction "2_2") (pintype "passive"))
      (node (ref "C7") (pin "2") (pinfunction "2_2") (pintype "passive"))
      (node (ref "C8") (pin "2") (pinfunction "2_2") (pintype "passive"))
      (node (ref "C9") (pin "2") (pinfunction "2_2") (pintype "passive"))
      (node (ref "CAN") (pin "6") (pinfunction "S_6") (pintype "passive"))
      (node (ref "D1") (pin "3") (pinfunction "CC_3") (pintype "bidirectional"))
      (node (ref "D2") (pin "3") (pinfunction "CC_3") (pintype "bidirectional"))
      (node (ref "ESP-01") (pin "2") (pinfunction "2_2") (pintype "passive"))
      (node (ref "IC1") (pin "2") (pinfunction "GND_2") (pintype "bidirectional"))
      (node (ref "IC2") (pin "2") (pinfunction "GND_2") (pintype "bidirectional"))
      (node (ref "IC3") (pin "9") (pinfunction "VSS_9") (pintype "power_in"))
      (node (ref "IC5") (pin "2") (pinfunction "GND_2") (pintype "bidirectional"))
      (node (ref "IC6") (pin "2") (pinfunction "GND_2") (pintype "bidirectional"))
      (node (ref "IC9") (pin "2") (pinfunction "GND_2") (pintype "bidirectional"))
      (node (ref "J1") (pin "P6") (pinfunction "VSS_P6") (pintype "bidirectional"))
      (node (ref "LED1") (pin "C") (pinfunction "C_C") (pintype "passive"))
      (node (ref "LED2") (pin "C") (pinfunction "C_C") (pintype "passive"))
      (node (ref "PILHA") (pin "1") (pinfunction "1_1") (pintype "passive"))
      (node (ref "PILHA") (pin "2") (pinfunction "2_2") (pintype "passive"))
      (node (ref "PILHA") (pin "3") (pinfunction "3_3") (pintype "passive"))
      (node (ref "PILHA") (pin "4") (pinfunction "4_4") (pintype "passive"))
      (node (ref "R29") (pin "1") (pinfunction "1_1") (pintype "passive"))
      (node (ref "R32") (pin "1") (pinfunction "1_1") (pintype "passive"))
      (node (ref "R35") (pin "1") (pinfunction "1_1") (pintype "passive"))
      (node (ref "R36") (pin "1") (pinfunction "1_1") (pintype "passive"))
      (node (ref "R37") (pin "1") (pinfunction "1_1") (pintype "passive"))
      (node (ref "R38") (pin "1") (pinfunction "1_1") (pintype "passive"))
      (node (ref "R39") (pin "1") (pinfunction "1_1") (pintype "passive"))
      (node (ref "R40") (pin "1") (pinfunction "1_1") (pintype "passive"))
      (node (ref "R41") (pin "1") (pinfunction "1_1") (pintype "passive"))
      (node (ref "R42") (pin "1") (pinfunction "1_1") (pintype "passive"))
      (node (ref "R43") (pin "1") (pinfunction "1_1") (pintype "passive"))
      (node (ref "R44") (pin "1") (pinfunction "1_1") (pintype "passive"))
      (node (ref "R45") (pin "1") (pinfunction "1_1") (pintype "passive"))
      (node (ref "R46") (pin "1") (pinfunction "1_1") (pintype "passive"))
      (node (ref "R47") (pin "1") (pinfunction "1_1") (pintype "passive"))
      (node (ref "S1") (pin "1") (pinfunction "1_1") (pintype "passive"))
      (node (ref "U1") (pin "D8") (pinfunction "DGND_D8") (pintype "bidirectional"))
      (node (ref "U1") (pin "D9") (pinfunction "DGND_D9") (pintype "bidirectional"))
      (node (ref "U1") (pin "E10") (pinfunction "DGND_E10") (pintype "bidirectional"))
      (node (ref "U1") (pin "E11") (pinfunction "DGND_E11") (pintype "bidirectional"))
      (node (ref "U1") (pin "E12") (pinfunction "DGND_E12") (pintype "bidirectional"))
      (node (ref "U1") (pin "E5") (pinfunction "DGND_E5") (pintype "bidirectional"))
      (node (ref "U1") (pin "E6") (pinfunction "DGND_E6") (pintype "bidirectional"))
      (node (ref "U1") (pin "E7") (pinfunction "DGND_E7") (pintype "bidirectional"))
      (node (ref "U1") (pin "E8") (pinfunction "DGND_E8") (pintype "bidirectional"))
      (node (ref "U1") (pin "E9") (pinfunction "DGND_E9") (pintype "bidirectional"))
      (node (ref "U1") (pin "F12") (pinfunction "DGND_F12") (pintype "bidirectional"))
      (node (ref "U1") (pin "F5") (pinfunction "DGND_F5") (pintype "bidirectional"))
      (node (ref "U1") (pin "G12") (pinfunction "DGND_G12") (pintype "bidirectional"))
      (node (ref "U1") (pin "G5") (pinfunction "DGND_G5") (pintype "bidirectional"))
      (node (ref "U1") (pin "H12") (pinfunction "DGND_H12") (pintype "bidirectional"))
      (node (ref "U1") (pin "H13") (pinfunction "DGND_H13") (pintype "bidirectional"))
      (node (ref "U1") (pin "H4") (pinfunction "DGND_H4") (pintype "bidirectional"))
      (node (ref "U1") (pin "H5") (pinfunction "DGND_H5") (pintype "bidirectional"))
      (node (ref "U1") (pin "J12") (pinfunction "DGND_J12") (pintype "bidirectional"))
      (node (ref "U1") (pin "J13") (pinfunction "DGND_J13") (pintype "bidirectional"))
      (node (ref "U1") (pin "J4") (pinfunction "DGND_J4") (pintype "bidirectional"))
      (node (ref "U1") (pin "J5") (pinfunction "DGND_J5") (pintype "bidirectional"))
      (node (ref "U1") (pin "K12") (pinfunction "DGND_K12") (pintype "bidirectional"))
      (node (ref "U1") (pin "K5") (pinfunction "DGND_K5") (pintype "bidirectional"))
      (node (ref "U1") (pin "L12") (pinfunction "DGND_L12") (pintype "bidirectional"))
      (node (ref "U1") (pin "L5") (pinfunction "DGND_L5") (pintype "bidirectional"))
      (node (ref "U1") (pin "M10") (pinfunction "DGND_M10") (pintype "bidirectional"))
      (node (ref "U1") (pin "M11") (pinfunction "DGND_M11") (pintype "bidirectional"))
      (node (ref "U1") (pin "M12") (pinfunction "DGND_M12") (pintype "bidirectional"))
      (node (ref "U1") (pin "M5") (pinfunction "DGND_M5") (pintype "bidirectional"))
      (node (ref "U1") (pin "M6") (pinfunction "DGND_M6") (pintype "bidirectional"))
      (node (ref "U1") (pin "M7") (pinfunction "DGND_M7") (pintype "bidirectional"))
      (node (ref "U1") (pin "M8") (pinfunction "DGND_M8") (pintype "bidirectional"))
      (node (ref "U1") (pin "M9") (pinfunction "DGND_M9") (pintype "bidirectional"))
      (node (ref "U1") (pin "N8") (pinfunction "DGND_N8") (pintype "bidirectional"))
      (node (ref "U1") (pin "N9") (pinfunction "DGND_N9") (pintype "bidirectional"))
      (node (ref "U2") (pin "14") (pinfunction "14-GND_14") (pintype "bidirectional"))
      (node (ref "U2") (pin "20") (pinfunction "20-GND_20") (pintype "bidirectional"))
      (node (ref "U2") (pin "25") (pinfunction "25-GND_25") (pintype "bidirectional"))
      (node (ref "U2") (pin "30") (pinfunction "30-GND_30") (pintype "bidirectional"))
      (node (ref "U2") (pin "34") (pinfunction "34-GND_34") (pintype "bidirectional"))
      (node (ref "U2") (pin "39") (pinfunction "39-GND_39") (pintype "bidirectional"))
      (node (ref "U2") (pin "6") (pinfunction "6-GND_6") (pintype "bidirectional"))
      (node (ref "U2") (pin "9") (pinfunction "9-GND_9") (pintype "bidirectional"))
      (node (ref "U4") (pin "3") (pinfunction "GND_3") (pintype "bidirectional"))
      (node (ref "USB1") (pin "1") (pinfunction "S_1") (pintype "passive"))
      (node (ref "USB2") (pin "1") (pinfunction "S_1") (pintype "passive"))
      (node (ref "Y3") (pin "2") (pinfunction "GND_1_2") (pintype "bidirectional"))
      (node (ref "Y3") (pin "4") (pinfunction "GND_2_4") (pintype "bidirectional"))
    )
    (net (code "51") (name "GPIO0") (class "Default")
      (node (ref "ESP-01") (pin "6") (pinfunction "6_6") (pintype "passive"))
      (node (ref "U1") (pin "B3") (pinfunction "MCASP0_FSR_B3") (pintype "bidirectional"))
      (node (ref "U2") (pin "12") (pinfunction "12-GPIO18_12") (pintype "bidirectional"))
    )
    (net (code "52") (name "GPIO2") (class "Default")
      (node (ref "ESP-01") (pin "4") (pinfunction "4_4") (pintype "passive"))
      (node (ref "U1") (pin "C4") (pinfunction "MCASP0_AHCLKX_C4") (pintype "bidirectional"))
      (node (ref "U2") (pin "7") (pinfunction "7-GPIO4_7") (pintype "bidirectional"))
    )
    (net (code "53") (name "GPIO6") (class "Default")
      (node (ref "U2") (pin "31") (pinfunction "31-GPIO6_31") (pintype "bidirectional"))
    )
    (net (code "54") (name "GPIO19") (class "Default")
      (node (ref "U2") (pin "35") (pinfunction "35-GPIO19_35") (pintype "bidirectional"))
    )
    (net (code "55") (name "GPIO20P") (class "Default")
      (node (ref "DEBUG1") (pin "1") (pinfunction "1_1") (pintype "passive"))
      (node (ref "U1") (pin "B4") (pinfunction "XDMA_EVENT_INTR1_B4") (pintype "bidirectional"))
    )
    (net (code "56") (name "GPIO23") (class "Default")
      (node (ref "CAN") (pin "2") (pinfunction "S_2") (pintype "passive"))
      (node (ref "U1") (pin "P5") (pinfunction "GPMC_AD9_P5") (pintype "bidirectional"))
      (node (ref "U2") (pin "36") (pinfunction "36-GPIO16_36") (pintype "bidirectional"))
    )
    (net (code "57") (name "GPIO26") (class "Default")
      (node (ref "CAN") (pin "1") (pinfunction "S_1") (pintype "passive"))
      (node (ref "U1") (pin "R5") (pinfunction "GPMC_AD10_R5") (pintype "bidirectional"))
      (node (ref "U2") (pin "38") (pinfunction "38-GPIO20_38") (pintype "bidirectional"))
    )
    (net (code "58") (name "GPIO26R") (class "Default")
      (node (ref "U2") (pin "37") (pinfunction "37-GPIO26_37") (pintype "bidirectional"))
    )
    (net (code "59") (name "GPIO27") (class "Default")
      (node (ref "U1") (pin "T5") (pinfunction "GPMC_AD11_T5") (pintype "bidirectional"))
      (node (ref "U2") (pin "40") (pinfunction "40-GPIO21_40") (pintype "bidirectional"))
    )
    (net (code "60") (name "GPIO44") (class "Default")
      (node (ref "U1") (pin "P6") (pinfunction "GPMC_AD12_P6") (pintype "bidirectional"))
    )
    (net (code "61") (name "GPIO45") (class "Default")
      (node (ref "U1") (pin "R6") (pinfunction "GPMC_AD13_R6") (pintype "bidirectional"))
    )
    (net (code "62") (name "GPIO46") (class "Default")
      (node (ref "DEBUG2") (pin "1") (pinfunction "1_1") (pintype "passive"))
      (node (ref "U1") (pin "T6") (pinfunction "GPMC_AD14_T6") (pintype "bidirectional"))
    )
    (net (code "63") (name "GPIO47") (class "Default")
      (node (ref "U1") (pin "P7") (pinfunction "GPMC_AD15_P7") (pintype "bidirectional"))
    )
    (net (code "64") (name "GPIO52") (class "Default")
      (node (ref "U1") (pin "R13") (pinfunction "GPMC_A4_R13") (pintype "bidirectional"))
    )
    (net (code "65") (name "GPIO57") (class "Default")
      (node (ref "U1") (pin "T15") (pinfunction "GPMC_A9_T15") (pintype "bidirectional"))
    )
    (net (code "66") (name "GPIO58") (class "Default")
      (node (ref "U1") (pin "R15") (pinfunction "GPMC_A10_R15") (pintype "bidirectional"))
    )
    (net (code "67") (name "GPIO59") (class "Default")
      (node (ref "U1") (pin "T16") (pinfunction "GPMC_A11_T16") (pintype "bidirectional"))
    )
    (net (code "68") (name "GPIO60") (class "Default")
      (node (ref "U1") (pin "N14") (pinfunction "GPMC_BEN1_N14") (pintype "bidirectional"))
    )
    (net (code "69") (name "GPIO64") (class "Default")
      (node (ref "DEBUG") (pin "2") (pinfunction "2_2") (pintype "passive"))
      (node (ref "U1") (pin "R7") (pinfunction "GPMC_CSN3_R7") (pintype "bidirectional"))
    )
    (net (code "70") (name "GPIO65") (class "Default")
      (node (ref "DEBUG") (pin "1") (pinfunction "1_1") (pintype "passive"))
      (node (ref "U1") (pin "T7") (pinfunction "GPMC_CLK_T7") (pintype "bidirectional"))
    )
    (net (code "71") (name "GPIO87") (class "Default")
      (node (ref "U1") (pin "F2") (pinfunction "LCD_HSYNC_F2") (pintype "bidirectional"))
    )
    (net (code "72") (name "GPIO89") (class "Default")
      (node (ref "U1") (pin "E1") (pinfunction "LCD_AC_BIAS_EN_E1") (pintype "bidirectional"))
    )
    (net (code "73") (name "ID0") (class "Default")
      (node (ref "IC2") (pin "3") (pinfunction "D2+_3") (pintype "bidirectional"))
      (node (ref "U1") (pin "K14") (pinfunction "USB0_ID_K14") (pintype "bidirectional"))
      (node (ref "USB1") (pin "2") (pinfunction "S_2") (pintype "passive"))
    )
    (net (code "74") (name "ID1") (class "Default")
      (node (ref "IC6") (pin "3") (pinfunction "D2+_3") (pintype "bidirectional"))
      (node (ref "U1") (pin "L14") (pinfunction "USB1_ID_L14") (pintype "bidirectional"))
      (node (ref "USB2") (pin "2") (pinfunction "S_2") (pintype "passive"))
    )
    (net (code "75") (name "ID_SC") (class "Default")
      (node (ref "U2") (pin "28") (pinfunction "28-ID_SC_28") (pintype "bidirectional"))
    )
    (net (code "76") (name "ID_SD") (class "Default")
      (node (ref "U2") (pin "27") (pinfunction "27-ID_SD_27") (pintype "bidirectional"))
    )
    (net (code "77") (name "MISO") (class "Default")
      (node (ref "IC3") (pin "15") (pinfunction "SO_15") (pintype "bidirectional"))
      (node (ref "U2") (pin "21") (pinfunction "21-SPI-MISO/GPIO9_21") (pintype "bidirectional"))
    )
    (net (code "78") (name "MISO1") (class "Default")
      (node (ref "PILHA") (pin "13") (pinfunction "13_13") (pintype "passive"))
    )
    (net (code "79") (name "MOSI") (class "Default")
      (node (ref "IC3") (pin "14") (pinfunction "SI_14") (pintype "bidirectional"))
      (node (ref "U2") (pin "19") (pinfunction "19-SPI-MOSI/GPIO10_19") (pintype "bidirectional"))
    )
    (net (code "80") (name "MOSI1") (class "Default")
      (node (ref "PILHA") (pin "14") (pinfunction "14_14") (pintype "passive"))
    )
    (net (code "81") (name "MP1") (class "Default")
      (node (ref "J1") (pin "MP1") (pinfunction "MP1_MP1") (pintype "bidirectional"))
    )
    (net (code "82") (name "MP2") (class "Default")
      (node (ref "J1") (pin "MP2") (pinfunction "MP2_MP2") (pintype "bidirectional"))
    )
    (net (code "83") (name "MP3") (class "Default")
      (node (ref "J1") (pin "MP3") (pinfunction "MP3_MP3") (pintype "bidirectional"))
    )
    (net (code "84") (name "MP4") (class "Default")
      (node (ref "J1") (pin "MP4") (pinfunction "MP4_MP4") (pintype "bidirectional"))
    )
    (net (code "85") (name "Net-(C11-Pad1)") (class "Default")
      (node (ref "C11") (pin "1") (pinfunction "1_1") (pintype "passive"))
      (node (ref "R3") (pin "1") (pinfunction "1_1") (pintype "passive"))
      (node (ref "R4") (pin "2") (pinfunction "2_2") (pintype "passive"))
    )
    (net (code "86") (name "Net-(DEBUG1-Pad2)") (class "Default")
      (node (ref "DEBUG1") (pin "2") (pinfunction "2_2") (pintype "passive"))
      (node (ref "R1") (pin "2") (pinfunction "2_2") (pintype "passive"))
    )
    (net (code "87") (name "Net-(DEBUG2-Pad2)") (class "Default")
      (node (ref "DEBUG2") (pin "2") (pinfunction "2_2") (pintype "passive"))
      (node (ref "R2") (pin "2") (pinfunction "2_2") (pintype "passive"))
    )
    (net (code "88") (name "Net-(IC3-OSC1)") (class "Default")
      (node (ref "C5") (pin "1") (pinfunction "1_1") (pintype "passive"))
      (node (ref "IC3") (pin "8") (pinfunction "OSC1_8") (pintype "bidirectional"))
      (node (ref "Y3") (pin "3") (pinfunction "CRYSTAL_2_3") (pintype "bidirectional"))
    )
    (net (code "89") (name "Net-(IC3-OSC2)") (class "Default")
      (node (ref "C4") (pin "1") (pinfunction "1_1") (pintype "passive"))
      (node (ref "IC3") (pin "7") (pinfunction "OSC2_7") (pintype "bidirectional"))
      (node (ref "Y3") (pin "1") (pinfunction "CRYSTAL_1_1") (pintype "bidirectional"))
    )
    (net (code "90") (name "Net-(IC3-RXCAN)") (class "Default")
      (node (ref "IC3") (pin "2") (pinfunction "RXCAN_2") (pintype "bidirectional"))
      (node (ref "IC9") (pin "4") (pinfunction "RXD_4") (pintype "bidirectional"))
    )
    (net (code "91") (name "Net-(IC3-TXCAN)") (class "Default")
      (node (ref "IC3") (pin "1") (pinfunction "TXCAN_1") (pintype "bidirectional"))
      (node (ref "IC9") (pin "1") (pinfunction "TXD_1") (pintype "bidirectional"))
    )
    (net (code "92") (name "Net-(LED1-PadA)") (class "Default")
      (node (ref "LED1") (pin "A") (pinfunction "A_A") (pintype "passive"))
      (node (ref "R1") (pin "1") (pinfunction "1_1") (pintype "passive"))
    )
    (net (code "93") (name "Net-(LED2-PadA)") (class "Default")
      (node (ref "LED2") (pin "A") (pinfunction "A_A") (pintype "passive"))
      (node (ref "R2") (pin "1") (pinfunction "1_1") (pintype "passive"))
    )
    (net (code "94") (name "Net-(PWR-PadA)") (class "Default")
      (node (ref "PWR") (pin "A") (pinfunction "A_A") (pintype "passive"))
      (node (ref "U1") (pin "F11") (pinfunction "SYS_VDD2_3P3V_F11") (pintype "power_in"))
      (node (ref "U1") (pin "G11") (pinfunction "SYS_VDD2_3P3V_G11") (pintype "power_in"))
    )
    (net (code "95") (name "Net-(PWR-PadC)") (class "Default")
      (node (ref "PWR") (pin "C") (pinfunction "C_C") (pintype "passive"))
      (node (ref "R32") (pin "2") (pinfunction "2_2") (pintype "passive"))
    )
    (net (code "96") (name "Net-(U1A-EXTINTN)") (class "Default")
      (node (ref "U1") (pin "D4") (pinfunction "EXTINTN_D4") (pintype "bidirectional"))
      (node (ref "U1") (pin "E4") (pinfunction "PMIC_NINT_E4") (pintype "output"))
    )
    (net (code "97") (name "Net-(U1A-EXT_WAKEUP)") (class "Default")
      (node (ref "U1") (pin "L4") (pinfunction "PMIC_NWAKEUP_L4") (pintype "output"))
      (node (ref "U1") (pin "M4") (pinfunction "EXT_WAKEUP_M4") (pintype "bidirectional"))
    )
    (net (code "98") (name "Net-(U1A-PMIC_LDO_PGOOD)") (class "Default")
      (node (ref "U1") (pin "N4") (pinfunction "PMIC_LDO_PGOOD_N4") (pintype "output"))
      (node (ref "U1") (pin "N5") (pinfunction "RTC_PWRONRSTN_N5") (pintype "bidirectional"))
    )
    (net (code "99") (name "Net-(U1A-PMIC_PB_IN)") (class "Default")
      (node (ref "S1") (pin "2") (pinfunction "2_2") (pintype "passive"))
      (node (ref "U1") (pin "T11") (pinfunction "PMIC_PB_IN_T11") (pintype "bidirectional"))
    )
    (net (code "100") (name "Net-(U1A-PMIC_PGOOD)") (class "Default")
      (node (ref "U1") (pin "N12") (pinfunction "PMIC_PGOOD_N12") (pintype "output"))
      (node (ref "U1") (pin "P11") (pinfunction "PWRONRSTN_P11") (pintype "bidirectional"))
      (node (ref "U4") (pin "2") (pinfunction "A_2") (pintype "bidirectional"))
    )
    (net (code "101") (name "Net-(U1A-PMIC_POWER_EN)") (class "Default")
      (node (ref "U1") (pin "N10") (pinfunction "PMIC_POWER_EN_N10") (pintype "output"))
      (node (ref "U1") (pin "N11") (pinfunction "PMIC_PWR_EN_N11") (pintype "input"))
    )
    (net (code "102") (name "Net-(U1A-RTC_KALDO_ENN)") (class "Default")
      (node (ref "R29") (pin "2") (pinfunction "2_2") (pintype "passive"))
      (node (ref "U1") (pin "M16") (pinfunction "RTC_KALDO_ENN_M16") (pintype "bidirectional"))
    )
    (net (code "103") (name "Net-(U1A-SYS_VDD_1P8V-PadF10)") (class "Default")
      (node (ref "U1") (pin "F10") (pinfunction "SYS_VDD_1P8V_F10") (pintype "power_in"))
      (node (ref "U1") (pin "G10") (pinfunction "SYS_VDD_1P8V_G10") (pintype "power_in"))
      (node (ref "U1") (pin "H10") (pinfunction "SYS_VDD_1P8V_H10") (pintype "power_in"))
      (node (ref "U1") (pin "H11") (pinfunction "SYS_VDD_1P8V_H11") (pintype "power_in"))
      (node (ref "U1") (pin "J10") (pinfunction "SYS_VDD_1P8V_J10") (pintype "power_in"))
      (node (ref "U1") (pin "J11") (pinfunction "SYS_VDD_1P8V_J11") (pintype "power_in"))
      (node (ref "U1") (pin "K10") (pinfunction "SYS_VDD_1P8V_K10") (pintype "power_in"))
      (node (ref "U1") (pin "L10") (pinfunction "SYS_VDD_1P8V_L10") (pintype "power_in"))
    )
    (net (code "104") (name "Net-(U1A-VDDSHV1)") (class "Default")
      (node (ref "U1") (pin "F8") (pinfunction "SYS_VDD3_3P3V_F8") (pintype "power_in"))
      (node (ref "U1") (pin "F9") (pinfunction "VDDSHV4_F9") (pintype "power_in"))
      (node (ref "U1") (pin "G8") (pinfunction "SYS_VDD3_3P3V_G8") (pintype "power_in"))
      (node (ref "U1") (pin "G9") (pinfunction "VDDSHV5_G9") (pintype "power_in"))
      (node (ref "U1") (pin "H7") (pinfunction "SYS_VDD3_3P3V_H7") (pintype "power_in"))
      (node (ref "U1") (pin "H8") (pinfunction "SYS_VDD3_3P3V_H8") (pintype "power_in"))
      (node (ref "U1") (pin "H9") (pinfunction "VDDSHV6_H9") (pintype "power_in"))
      (node (ref "U1") (pin "J7") (pinfunction "SYS_VDD3_3P3V_J7") (pintype "power_in"))
      (node (ref "U1") (pin "J8") (pinfunction "SYS_VDD3_3P3V_J8") (pintype "power_in"))
      (node (ref "U1") (pin "J9") (pinfunction "VDDSHV1_J9") (pintype "power_in"))
      (node (ref "U1") (pin "K8") (pinfunction "SYS_VDD3_3P3V_K8") (pintype "power_in"))
      (node (ref "U1") (pin "K9") (pinfunction "VDDSHV2_K9") (pintype "power_in"))
      (node (ref "U1") (pin "L8") (pinfunction "SYS_VDD3_3P3V_L8") (pintype "power_in"))
      (node (ref "U1") (pin "L9") (pinfunction "VDDSHV3_L9") (pintype "power_in"))
    )
    (net (code "105") (name "Net-(U1A-WARMRSTN)") (class "Default")
      (node (ref "U1") (pin "R11") (pinfunction "WARMRSTN_R11") (pintype "bidirectional"))
      (node (ref "U4") (pin "4") (pinfunction "Y_4") (pintype "bidirectional"))
    )
    (net (code "106") (name "Net-(U1B-AGND_ADC)") (class "Default")
      (node (ref "C27") (pin "2") (pinfunction "2_2") (pintype "passive"))
      (node (ref "U1") (pin "A9") (pinfunction "AGND_ADC_A9") (pintype "bidirectional"))
      (node (ref "U1") (pin "B9") (pinfunction "VREFN_B9") (pintype "bidirectional"))
    )
    (net (code "107") (name "Net-(U1B-AIN7)") (class "Default")
      (node (ref "U1") (pin "D6") (pinfunction "PMIC_MUX_OUT_D6") (pintype "bidirectional"))
      (node (ref "U1") (pin "D7") (pinfunction "AIN7_D7") (pintype "bidirectional"))
    )
    (net (code "108") (name "Net-(U1B-OSC0_GND)") (class "Default")
      (node (ref "C22") (pin "2") (pinfunction "2_2") (pintype "passive"))
      (node (ref "C24") (pin "2") (pinfunction "2_2") (pintype "passive"))
      (node (ref "U1") (pin "N15") (pinfunction "OSC0_GND_N15") (pintype "bidirectional"))
      (node (ref "Y1") (pin "2") (pinfunction "GND_1_2") (pintype "bidirectional"))
      (node (ref "Y1") (pin "4") (pinfunction "GND_2_4") (pintype "bidirectional"))
    )
    (net (code "109") (name "Net-(U1B-OSC0_IN)") (class "Default")
      (node (ref "C22") (pin "1") (pinfunction "1_1") (pintype "passive"))
      (node (ref "R33") (pin "2") (pinfunction "2_2") (pintype "passive"))
      (node (ref "U1") (pin "P16") (pinfunction "OSC0_IN_P16") (pintype "bidirectional"))
      (node (ref "Y1") (pin "1") (pinfunction "CRYSTAL_1_1") (pintype "bidirectional"))
    )
    (net (code "110") (name "Net-(U1B-OSC0_OUT)") (class "Default")
      (node (ref "C24") (pin "1") (pinfunction "1_1") (pintype "passive"))
      (node (ref "R33") (pin "1") (pinfunction "1_1") (pintype "passive"))
      (node (ref "U1") (pin "N16") (pinfunction "OSC0_OUT_N16") (pintype "bidirectional"))
      (node (ref "Y1") (pin "3") (pinfunction "CRYSTAL_2_3") (pintype "bidirectional"))
    )
    (net (code "111") (name "Net-(U1B-OSC1_GND)") (class "Default")
      (node (ref "C25") (pin "2") (pinfunction "2_2") (pintype "passive"))
      (node (ref "C26") (pin "2") (pinfunction "2_2") (pintype "passive"))
      (node (ref "U1") (pin "B5") (pinfunction "OSC1_GND_B5") (pintype "bidirectional"))
    )
    (net (code "112") (name "Net-(U1B-OSC1_IN)") (class "Default")
      (node (ref "C25") (pin "1") (pinfunction "1_1") (pintype "passive"))
      (node (ref "R34") (pin "2") (pinfunction "2_2") (pintype "passive"))
      (node (ref "U1") (pin "A6") (pinfunction "OSC1_IN_A6") (pintype "bidirectional"))
      (node (ref "Y2") (pin "P$1") (pinfunction "1_P$1") (pintype "passive"))
    )
    (net (code "113") (name "Net-(U1B-OSC1_OUT)") (class "Default")
      (node (ref "C26") (pin "1") (pinfunction "1_1") (pintype "passive"))
      (node (ref "R34") (pin "1") (pinfunction "1_1") (pintype "passive"))
      (node (ref "U1") (pin "A5") (pinfunction "OSC1_OUT_A5") (pintype "bidirectional"))
      (node (ref "Y2") (pin "P$4") (pinfunction "2_P$4") (pintype "passive"))
    )
    (net (code "114") (name "Net-(U1B-SYS_ADC_1P8V)") (class "Default")
      (node (ref "C27") (pin "1") (pinfunction "1_1") (pintype "passive"))
      (node (ref "U1") (pin "A7") (pinfunction "SYS_ADC_1P8V_A7") (pintype "bidirectional"))
      (node (ref "U1") (pin "B7") (pinfunction "VREFP_B7") (pintype "bidirectional"))
    )
    (net (code "115") (name "Net-(U1D-LCD_DATA0)") (class "Default")
      (node (ref "R47") (pin "2") (pinfunction "2_2") (pintype "passive"))
      (node (ref "U1") (pin "G3") (pinfunction "LCD_DATA0_G3") (pintype "bidirectional"))
    )
    (net (code "116") (name "Net-(U1D-LCD_DATA1)") (class "Default")
      (node (ref "R46") (pin "2") (pinfunction "2_2") (pintype "passive"))
      (node (ref "U1") (pin "G2") (pinfunction "LCD_DATA1_G2") (pintype "bidirectional"))
    )
    (net (code "117") (name "Net-(U1D-LCD_DATA2)") (class "Default")
      (node (ref "R45") (pin "2") (pinfunction "2_2") (pintype "passive"))
      (node (ref "U1") (pin "G1") (pinfunction "LCD_DATA2_G1") (pintype "bidirectional"))
    )
    (net (code "118") (name "Net-(U1D-LCD_DATA3)") (class "Default")
      (node (ref "R48") (pin "1") (pinfunction "1_1") (pintype "passive"))
      (node (ref "U1") (pin "H3") (pinfunction "LCD_DATA3_H3") (pintype "bidirectional"))
    )
    (net (code "119") (name "Net-(U1D-LCD_DATA4)") (class "Default")
      (node (ref "R49") (pin "1") (pinfunction "1_1") (pintype "passive"))
      (node (ref "U1") (pin "H2") (pinfunction "LCD_DATA4_H2") (pintype "bidirectional"))
    )
    (net (code "120") (name "Net-(U1D-LCD_DATA5)") (class "Default")
      (node (ref "R44") (pin "2") (pinfunction "2_2") (pintype "passive"))
      (node (ref "U1") (pin "H1") (pinfunction "LCD_DATA5_H1") (pintype "bidirectional"))
    )
    (net (code "121") (name "Net-(U1D-LCD_DATA6)") (class "Default")
      (node (ref "R43") (pin "2") (pinfunction "2_2") (pintype "passive"))
      (node (ref "U1") (pin "J3") (pinfunction "LCD_DATA6_J3") (pintype "bidirectional"))
    )
    (net (code "122") (name "Net-(U1D-LCD_DATA7)") (class "Default")
      (node (ref "R42") (pin "2") (pinfunction "2_2") (pintype "passive"))
      (node (ref "U1") (pin "J2") (pinfunction "LCD_DATA7_J2") (pintype "bidirectional"))
    )
    (net (code "123") (name "Net-(U1D-LCD_DATA8)") (class "Default")
      (node (ref "R41") (pin "2") (pinfunction "2_2") (pintype "passive"))
      (node (ref "U1") (pin "J1") (pinfunction "LCD_DATA8_J1") (pintype "bidirectional"))
    )
    (net (code "124") (name "Net-(U1D-LCD_DATA9)") (class "Default")
      (node (ref "R40") (pin "2") (pinfunction "2_2") (pintype "passive"))
      (node (ref "U1") (pin "K3") (pinfunction "LCD_DATA9_K3") (pintype "bidirectional"))
    )
    (net (code "125") (name "Net-(U1D-LCD_DATA10)") (class "Default")
      (node (ref "R39") (pin "2") (pinfunction "2_2") (pintype "passive"))
      (node (ref "U1") (pin "K2") (pinfunction "LCD_DATA10_K2") (pintype "bidirectional"))
    )
    (net (code "126") (name "Net-(U1D-LCD_DATA11)") (class "Default")
      (node (ref "R38") (pin "2") (pinfunction "2_2") (pintype "passive"))
      (node (ref "U1") (pin "K1") (pinfunction "LCD_DATA11_K1") (pintype "bidirectional"))
    )
    (net (code "127") (name "Net-(U1D-LCD_DATA12)") (class "Default")
      (node (ref "R37") (pin "2") (pinfunction "2_2") (pintype "passive"))
      (node (ref "U1") (pin "L3") (pinfunction "LCD_DATA12_L3") (pintype "bidirectional"))
    )
    (net (code "128") (name "Net-(U1D-LCD_DATA13)") (class "Default")
      (node (ref "R36") (pin "2") (pinfunction "2_2") (pintype "passive"))
      (node (ref "U1") (pin "L2") (pinfunction "LCD_DATA13_L2") (pintype "bidirectional"))
    )
    (net (code "129") (name "Net-(U1D-LCD_DATA14)") (class "Default")
      (node (ref "R50") (pin "1") (pinfunction "1_1") (pintype "passive"))
      (node (ref "U1") (pin "L1") (pinfunction "LCD_DATA14_L1") (pintype "bidirectional"))
    )
    (net (code "130") (name "Net-(U1D-LCD_DATA15)") (class "Default")
      (node (ref "R35") (pin "2") (pinfunction "2_2") (pintype "passive"))
      (node (ref "U1") (pin "M3") (pinfunction "LCD_DATA15_M3") (pintype "bidirectional"))
    )
    (net (code "131") (name "Net-(U2-1-3V3)") (class "Default")
      (node (ref "3V3") (pin "2") (pinfunction "2_2") (pintype "passive"))
      (node (ref "U2") (pin "1") (pinfunction "1-3V3_1") (pintype "bidirectional"))
      (node (ref "U2") (pin "17") (pinfunction "17-3V3_17") (pintype "bidirectional"))
    )
    (net (code "132") (name "Net-(U2-2-5V)") (class "Default")
      (node (ref "5V") (pin "1") (pinfunction "1_1") (pintype "passive"))
      (node (ref "U2") (pin "2") (pinfunction "2-5V_2") (pintype "bidirectional"))
      (node (ref "U2") (pin "4") (pinfunction "4-5V_4") (pintype "bidirectional"))
    )
    (net (code "133") (name "PRU1_10") (class "Default")
      (node (ref "U1") (pin "F1") (pinfunction "LCD_PCLK_F1") (pintype "bidirectional"))
    )
    (net (code "134") (name "PWM") (class "Default")
      (node (ref "PILHA") (pin "35") (pinfunction "35_35") (pintype "passive"))
      (node (ref "U1") (pin "A1") (pinfunction "MCASP0_ACLKX_A1") (pintype "bidirectional"))
      (node (ref "U2") (pin "32") (pinfunction "32-GPIO12_32") (pintype "bidirectional"))
    )
    (net (code "135") (name "PWM1") (class "Default")
      (node (ref "DEBUG") (pin "3") (pinfunction "3_3") (pintype "passive"))
      (node (ref "U1") (pin "P12") (pinfunction "GPMC_A2_P12") (pintype "bidirectional"))
    )
    (net (code "136") (name "PWM1R") (class "Default")
      (node (ref "U2") (pin "33") (pinfunction "33-GPIO13_33") (pintype "bidirectional"))
    )
    (net (code "137") (name "RESET") (class "Default")
      (node (ref "ESP-01") (pin "5") (pinfunction "5_5") (pintype "passive"))
      (node (ref "U1") (pin "C3") (pinfunction "MCASP0_AXR1_C3") (pintype "bidirectional"))
      (node (ref "U2") (pin "16") (pinfunction "16-GPIO23_16") (pintype "bidirectional"))
    )
    (net (code "138") (name "RX1") (class "Default")
      (node (ref "PILHA") (pin "28") (pinfunction "28_28") (pintype "passive"))
      (node (ref "U1") (pin "P15") (pinfunction "GPMC_WAIT0_P15") (pintype "bidirectional"))
      (node (ref "U2") (pin "8") (pinfunction "8-TX_8") (pintype "bidirectional"))
    )
    (net (code "139") (name "RX2") (class "Default")
      (node (ref "PILHA") (pin "30") (pinfunction "30_30") (pintype "passive"))
    )
    (net (code "140") (name "SCK1") (class "Default")
      (node (ref "PILHA") (pin "15") (pinfunction "15_15") (pintype "passive"))
    )
    (net (code "141") (name "SCL1") (class "Default")
      (node (ref "PILHA") (pin "19") (pinfunction "19_19") (pintype "passive"))
      (node (ref "U1") (pin "B11") (pinfunction "UART1_TXD_B11") (pintype "bidirectional"))
    )
    (net (code "142") (name "SCL2") (class "Default")
      (node (ref "PILHA") (pin "24") (pinfunction "24_24") (pintype "passive"))
      (node (ref "U1") (pin "C10") (pinfunction "I2C0_SCL_C10") (pintype "bidirectional"))
      (node (ref "U1") (pin "D10") (pinfunction "PMIC_SCL_D10") (pintype "bidirectional"))
    )
    (net (code "143") (name "SCL3") (class "Default")
      (node (ref "PILHA") (pin "26") (pinfunction "26_26") (pintype "passive"))
      (node (ref "U2") (pin "5") (pinfunction "5-SCL1/GPIO3_5") (pintype "bidirectional"))
    )
    (net (code "144") (name "SCLK") (class "Default")
      (node (ref "IC3") (pin "13") (pinfunction "SCK_13") (pintype "bidirectional"))
      (node (ref "U2") (pin "23") (pinfunction "23-SPI-SCLK/GPIO11_23") (pintype "bidirectional"))
    )
    (net (code "145") (name "SDA1") (class "Default")
      (node (ref "PILHA") (pin "17") (pinfunction "17_17") (pintype "passive"))
      (node (ref "U1") (pin "A11") (pinfunction "UART1_RXD_A11") (pintype "bidirectional"))
    )
    (net (code "146") (name "SDA2") (class "Default")
      (node (ref "PILHA") (pin "23") (pinfunction "23_23") (pintype "passive"))
      (node (ref "U1") (pin "C11") (pinfunction "I2C0_SDA_C11") (pintype "bidirectional"))
      (node (ref "U1") (pin "D11") (pinfunction "PMIC_SDA_D11") (pintype "bidirectional"))
    )
    (net (code "147") (name "SDA3") (class "Default")
      (node (ref "PILHA") (pin "25") (pinfunction "25_25") (pintype "passive"))
      (node (ref "U2") (pin "3") (pinfunction "3-SDA1/GPIO2_3") (pintype "bidirectional"))
    )
    (net (code "148") (name "SDMMC_CK") (class "Default")
      (node (ref "J1") (pin "P5") (pinfunction "CLK_P5") (pintype "bidirectional"))
      (node (ref "U1") (pin "B15") (pinfunction "MMC0_CLK_B15") (pintype "bidirectional"))
    )
    (net (code "149") (name "SDMMC_CMD") (class "Default")
      (node (ref "J1") (pin "P3") (pinfunction "CMD_P3") (pintype "bidirectional"))
      (node (ref "R10") (pin "1") (pinfunction "1_1") (pintype "passive"))
      (node (ref "U1") (pin "B16") (pinfunction "MMC0_CMD_B16") (pintype "bidirectional"))
    )
    (net (code "150") (name "SDMMC_D0") (class "Default")
      (node (ref "J1") (pin "P7") (pinfunction "DAT0_P7") (pintype "bidirectional"))
      (node (ref "R9") (pin "1") (pinfunction "1_1") (pintype "passive"))
      (node (ref "U1") (pin "A16") (pinfunction "MMC0_DAT0_A16") (pintype "bidirectional"))
    )
    (net (code "151") (name "SDMMC_D1") (class "Default")
      (node (ref "J1") (pin "P8") (pinfunction "DAT1_P8") (pintype "bidirectional"))
      (node (ref "R8") (pin "1") (pinfunction "1_1") (pintype "passive"))
      (node (ref "U1") (pin "A15") (pinfunction "MMC0_DAT1_A15") (pintype "bidirectional"))
    )
    (net (code "152") (name "SDMMC_D2") (class "Default")
      (node (ref "J1") (pin "P1") (pinfunction "DAT2_P1") (pintype "bidirectional"))
      (node (ref "R12") (pin "1") (pinfunction "1_1") (pintype "passive"))
      (node (ref "U1") (pin "C16") (pinfunction "MMC0_DAT2_C16") (pintype "bidirectional"))
    )
    (net (code "153") (name "SDMMC_D3") (class "Default")
      (node (ref "J1") (pin "P2") (pinfunction "CD/DAT3_P2") (pintype "bidirectional"))
      (node (ref "R11") (pin "1") (pinfunction "1_1") (pintype "passive"))
      (node (ref "U1") (pin "C15") (pinfunction "MMC0_DAT3_C15") (pintype "bidirectional"))
    )
    (net (code "154") (name "SOL+") (class "Default")
      (node (ref "PILHA") (pin "7") (pinfunction "7_7") (pintype "passive"))
    )
    (net (code "155") (name "SOL-") (class "Default")
      (node (ref "PILHA") (pin "8") (pinfunction "8_8") (pintype "passive"))
    )
    (net (code "156") (name "SPI0_CS0") (class "Default")
      (node (ref "U1") (pin "A14") (pinfunction "SPI0_CS0_A14") (pintype "bidirectional"))
    )
    (net (code "157") (name "SPI0_CS1") (class "Default")
      (node (ref "U1") (pin "C14") (pinfunction "SPI0_CS1_C14") (pintype "bidirectional"))
    )
    (net (code "158") (name "SPI0_MISO") (class "Default")
      (node (ref "U1") (pin "B13") (pinfunction "SPI0_D0_B13") (pintype "bidirectional"))
    )
    (net (code "159") (name "SPI0_MOSI") (class "Default")
      (node (ref "U1") (pin "B14") (pinfunction "SPI0_D1_B14") (pintype "bidirectional"))
    )
    (net (code "160") (name "SPI0_SCLK") (class "Default")
      (node (ref "U1") (pin "A13") (pinfunction "SPI0_SCLK_A13") (pintype "bidirectional"))
    )
    (net (code "161") (name "SYS_VOUT") (class "Default")
      (node (ref "C20") (pin "1") (pinfunction "1_1") (pintype "passive"))
      (node (ref "U1") (pin "K6") (pinfunction "SYS_VOUT_K6") (pintype "power_in"))
      (node (ref "U1") (pin "K7") (pinfunction "SYS_VOUT_K7") (pintype "power_in"))
      (node (ref "U1") (pin "L6") (pinfunction "SYS_VOUT_L6") (pintype "power_in"))
      (node (ref "U1") (pin "L7") (pinfunction "SYS_VOUT_L7") (pintype "power_in"))
    )
    (net (code "162") (name "TCK") (class "Default")
      (node (ref "U1") (pin "D1") (pinfunction "TCK_D1") (pintype "bidirectional"))
    )
    (net (code "163") (name "TDI") (class "Default")
      (node (ref "U1") (pin "C1") (pinfunction "TDI_C1") (pintype "bidirectional"))
    )
    (net (code "164") (name "TDO") (class "Default")
      (node (ref "U1") (pin "C2") (pinfunction "TDO_C2") (pintype "bidirectional"))
    )
    (net (code "165") (name "TMS") (class "Default")
      (node (ref "U1") (pin "D2") (pinfunction "TMS_D2") (pintype "bidirectional"))
    )
    (net (code "166") (name "TRSTN") (class "Default")
      (node (ref "U1") (pin "D3") (pinfunction "TRSTN_D3") (pintype "bidirectional"))
    )
    (net (code "167") (name "TX1") (class "Default")
      (node (ref "PILHA") (pin "27") (pinfunction "27_27") (pintype "passive"))
      (node (ref "U1") (pin "R16") (pinfunction "GPMC_WPN_R16") (pintype "bidirectional"))
      (node (ref "U2") (pin "10") (pinfunction "10-RX_10") (pintype "bidirectional"))
    )
    (net (code "168") (name "TX2") (class "Default")
      (node (ref "PILHA") (pin "29") (pinfunction "29_29") (pintype "passive"))
    )
    (net (code "169") (name "UART0_RX") (class "Default")
      (node (ref "ESP-01") (pin "1") (pinfunction "1_1") (pintype "passive"))
      (node (ref "U1") (pin "A12") (pinfunction "UART0_RXD_A12") (pintype "bidirectional"))
    )
    (net (code "170") (name "UART0_TX") (class "Default")
      (node (ref "ESP-01") (pin "8") (pinfunction "8_8") (pintype "passive"))
      (node (ref "U1") (pin "B12") (pinfunction "UART0_TXD_B12") (pintype "bidirectional"))
    )
    (net (code "171") (name "USR0") (class "Default")
      (node (ref "U1") (pin "P13") (pinfunction "GPMC_A5_P13") (pintype "bidirectional"))
    )
    (net (code "172") (name "USR1") (class "Default")
      (node (ref "U1") (pin "T14") (pinfunction "GPMC_A6_T14") (pintype "bidirectional"))
    )
    (net (code "173") (name "USR2") (class "Default")
      (node (ref "U1") (pin "R14") (pinfunction "GPMC_A7_R14") (pintype "bidirectional"))
    )
    (net (code "174") (name "USR3") (class "Default")
      (node (ref "U1") (pin "P14") (pinfunction "GPMC_A8_P14") (pintype "bidirectional"))
    )
    (net (code "175") (name "VBUS1") (class "Default")
      (node (ref "C7") (pin "1") (pinfunction "1_1") (pintype "passive"))
      (node (ref "IC6") (pin "5") (pinfunction "VCC_5") (pintype "bidirectional"))
      (node (ref "U1") (pin "M15") (pinfunction "USB1_VBUS_M15") (pintype "bidirectional"))
      (node (ref "USB2") (pin "5") (pinfunction "S_5") (pintype "passive"))
    )
    (net (code "176") (name "VDD_RTC") (class "Default")
      (node (ref "C21") (pin "1") (pinfunction "1_1") (pintype "passive"))
      (node (ref "U1") (pin "K11") (pinfunction "SYS_RTC_1P8V_K11") (pintype "power_in"))
      (node (ref "U1") (pin "L11") (pinfunction "SYS_RTC_1P8V_L11") (pintype "power_in"))
      (node (ref "U4") (pin "5") (pinfunction "VCC_5") (pintype "bidirectional"))
    )
    (net (code "177") (name "VIN_BAT") (class "Default")
      (node (ref "U1") (pin "N7") (pinfunction "PMIC_BAT_SENSE_N7") (pintype "bidirectional"))
      (node (ref "U1") (pin "P8") (pinfunction "VIN_BAT_P8") (pintype "power_in"))
      (node (ref "U1") (pin "R8") (pinfunction "VIN_BAT_R8") (pintype "power_in"))
      (node (ref "U1") (pin "T8") (pinfunction "VIN_BAT_T8") (pintype "power_in"))
    )
    (net (code "178") (name "VIN_USB") (class "Default")
      (node (ref "C2") (pin "1") (pinfunction "1_1") (pintype "passive"))
      (node (ref "IC2") (pin "5") (pinfunction "VCC_5") (pintype "bidirectional"))
      (node (ref "U1") (pin "J16") (pinfunction "USB0_VBUS_J16") (pintype "bidirectional"))
      (node (ref "U1") (pin "P9") (pinfunction "VIN_USB_P9") (pintype "power_in"))
      (node (ref "U1") (pin "R9") (pinfunction "VIN_USB_R9") (pintype "power_in"))
      (node (ref "U1") (pin "T9") (pinfunction "VIN_USB_T9") (pintype "power_in"))
      (node (ref "USB1") (pin "5") (pinfunction "S_5") (pintype "passive"))
    )
    (net (code "179") (name "unconnected-(IC1-S-Pad8)") (class "Default")
      (node (ref "IC1") (pin "8") (pinfunction "S_8") (pintype "bidirectional"))
    )
    (net (code "180") (name "unconnected-(IC1-SHDN-Pad5)") (class "Default")
      (node (ref "IC1") (pin "5") (pinfunction "SHDN_5") (pintype "bidirectional"))
    )
    (net (code "181") (name "unconnected-(IC2-D2--Pad4)") (class "Default")
      (node (ref "IC2") (pin "4") (pinfunction "D2-_4") (pintype "bidirectional"))
    )
    (net (code "182") (name "unconnected-(IC3-CLKOUT-Pad3)") (class "Default")
      (node (ref "IC3") (pin "3") (pinfunction "CLKOUT_3") (pintype "output"))
    )
    (net (code "183") (name "unconnected-(IC3-~{RX0BF}-Pad11)") (class "Default")
      (node (ref "IC3") (pin "11") (pinfunction "~{RX0BF}_11") (pintype "bidirectional"))
    )
    (net (code "184") (name "unconnected-(IC3-~{RX1BF}-Pad10)") (class "Default")
      (node (ref "IC3") (pin "10") (pinfunction "~{RX1BF}_10") (pintype "bidirectional"))
    )
    (net (code "185") (name "unconnected-(IC3-~{TX0RTS}-Pad4)") (class "Default")
      (node (ref "IC3") (pin "4") (pinfunction "~{TX0RTS}_4") (pintype "bidirectional"))
    )
    (net (code "186") (name "unconnected-(IC3-~{TX1RTS}-Pad5)") (class "Default")
      (node (ref "IC3") (pin "5") (pinfunction "~{TX1RTS}_5") (pintype "bidirectional"))
    )
    (net (code "187") (name "unconnected-(IC3-~{TX2RTS}-Pad6)") (class "Default")
      (node (ref "IC3") (pin "6") (pinfunction "~{TX2RTS}_6") (pintype "bidirectional"))
    )
    (net (code "188") (name "unconnected-(IC5-S-Pad8)") (class "Default")
      (node (ref "IC5") (pin "8") (pinfunction "S_8") (pintype "bidirectional"))
    )
    (net (code "189") (name "unconnected-(IC5-SHDN-Pad5)") (class "Default")
      (node (ref "IC5") (pin "5") (pinfunction "SHDN_5") (pintype "bidirectional"))
    )
    (net (code "190") (name "unconnected-(IC6-D2--Pad4)") (class "Default")
      (node (ref "IC6") (pin "4") (pinfunction "D2-_4") (pintype "bidirectional"))
    )
    (net (code "191") (name "unconnected-(IC9-S-Pad8)") (class "Default")
      (node (ref "IC9") (pin "8") (pinfunction "S_8") (pintype "bidirectional"))
    )
    (net (code "192") (name "unconnected-(IC9-SHDN-Pad5)") (class "Default")
      (node (ref "IC9") (pin "5") (pinfunction "SHDN_5") (pintype "bidirectional"))
    )
    (net (code "193") (name "unconnected-(U1A-PMIC_NRESET-PadM13)") (class "Default")
      (node (ref "U1") (pin "M13") (pinfunction "PMIC_NRESET_M13") (pintype "bidirectional"))
    )
    (net (code "194") (name "unconnected-(U1C-ECAP0_IN_PWM0_OUT-PadC5)") (class "Default")
      (node (ref "U1") (pin "C5") (pinfunction "ECAP0_IN_PWM0_OUT_C5") (pintype "bidirectional"))
    )
    (net (code "195") (name "unconnected-(U1C-GPMC_A0-PadT12)") (class "Default")
      (node (ref "U1") (pin "T12") (pinfunction "GPMC_A0_T12") (pintype "bidirectional"))
    )
    (net (code "196") (name "unconnected-(U1C-GPMC_A1-PadR12)") (class "Default")
      (node (ref "U1") (pin "R12") (pinfunction "GPMC_A1_R12") (pintype "bidirectional"))
    )
    (net (code "197") (name "unconnected-(U1C-GPMC_A3-PadT13)") (class "Default")
      (node (ref "U1") (pin "T13") (pinfunction "GPMC_A3_T13") (pintype "bidirectional"))
    )
    (net (code "198") (name "unconnected-(U1C-GPMC_AD0-PadR3)") (class "Default")
      (node (ref "U1") (pin "R3") (pinfunction "GPMC_AD0_R3") (pintype "bidirectional"))
    )
    (net (code "199") (name "unconnected-(U1C-GPMC_AD1-PadR2)") (class "Default")
      (node (ref "U1") (pin "R2") (pinfunction "GPMC_AD1_R2") (pintype "bidirectional"))
    )
    (net (code "200") (name "unconnected-(U1C-GPMC_AD2-PadR1)") (class "Default")
      (node (ref "U1") (pin "R1") (pinfunction "GPMC_AD2_R1") (pintype "bidirectional"))
    )
    (net (code "201") (name "unconnected-(U1C-GPMC_AD3-PadT3)") (class "Default")
      (node (ref "U1") (pin "T3") (pinfunction "GPMC_AD3_T3") (pintype "bidirectional"))
    )
    (net (code "202") (name "unconnected-(U1C-GPMC_AD4-PadT2)") (class "Default")
      (node (ref "U1") (pin "T2") (pinfunction "GPMC_AD4_T2") (pintype "bidirectional"))
    )
    (net (code "203") (name "unconnected-(U1C-GPMC_AD5-PadT1)") (class "Default")
      (node (ref "U1") (pin "T1") (pinfunction "GPMC_AD5_T1") (pintype "bidirectional"))
    )
    (net (code "204") (name "unconnected-(U1C-GPMC_AD6-PadP4)") (class "Default")
      (node (ref "U1") (pin "P4") (pinfunction "GPMC_AD6_P4") (pintype "bidirectional"))
    )
    (net (code "205") (name "unconnected-(U1C-GPMC_AD7-PadR4)") (class "Default")
      (node (ref "U1") (pin "R4") (pinfunction "GPMC_AD7_R4") (pintype "bidirectional"))
    )
    (net (code "206") (name "unconnected-(U1C-GPMC_AD8-PadT4)") (class "Default")
      (node (ref "U1") (pin "T4") (pinfunction "GPMC_AD8_T4") (pintype "bidirectional"))
    )
    (net (code "207") (name "unconnected-(U1C-GPMC_ADVN_ALE-PadM1)") (class "Default")
      (node (ref "U1") (pin "M1") (pinfunction "GPMC_ADVN_ALE_M1") (pintype "bidirectional"))
    )
    (net (code "208") (name "unconnected-(U1C-GPMC_CSN0-PadP3)") (class "Default")
      (node (ref "U1") (pin "P3") (pinfunction "GPMC_CSN0_P3") (pintype "bidirectional"))
    )
    (net (code "209") (name "unconnected-(U1C-GPMC_CSN1-PadP2)") (class "Default")
      (node (ref "U1") (pin "P2") (pinfunction "GPMC_CSN1_P2") (pintype "bidirectional"))
    )
    (net (code "210") (name "unconnected-(U1C-GPMC_CSN2-PadP1)") (class "Default")
      (node (ref "U1") (pin "P1") (pinfunction "GPMC_CSN2_P1") (pintype "bidirectional"))
    )
    (net (code "211") (name "unconnected-(U1C-GPMC_OEN_REN-PadN1)") (class "Default")
      (node (ref "U1") (pin "N1") (pinfunction "GPMC_OEN_REN_N1") (pintype "bidirectional"))
    )
    (net (code "212") (name "unconnected-(U1C-GPMC_WEN-PadN2)") (class "Default")
      (node (ref "U1") (pin "N2") (pinfunction "GPMC_WEN_N2") (pintype "bidirectional"))
    )
    (net (code "213") (name "unconnected-(U1C-XDMA_EVENT_INTR0-PadA4)") (class "Default")
      (node (ref "U1") (pin "A4") (pinfunction "XDMA_EVENT_INTR0_A4") (pintype "bidirectional"))
    )
    (net (code "214") (name "unconnected-(U1D-LCD_VSYNC-PadF3)") (class "Default")
      (node (ref "U1") (pin "F3") (pinfunction "LCD_VSYNC_F3") (pintype "bidirectional"))
    )
    (net (code "215") (name "unconnected-(U1D-MDC-PadD13)") (class "Default")
      (node (ref "U1") (pin "D13") (pinfunction "MDC_D13") (pintype "bidirectional"))
    )
    (net (code "216") (name "unconnected-(U1D-MDIO-PadE13)") (class "Default")
      (node (ref "U1") (pin "E13") (pinfunction "MDIO_E13") (pintype "bidirectional"))
    )
    (net (code "217") (name "unconnected-(U1D-MII1_COL-PadF15)") (class "Default")
      (node (ref "U1") (pin "F15") (pinfunction "MII1_COL_F15") (pintype "bidirectional"))
    )
    (net (code "218") (name "unconnected-(U1D-MII1_CRS-PadF14)") (class "Default")
      (node (ref "U1") (pin "F14") (pinfunction "MII1_CRS_F14") (pintype "bidirectional"))
    )
    (net (code "219") (name "unconnected-(U1D-MII1_RXD0-PadE14)") (class "Default")
      (node (ref "U1") (pin "E14") (pinfunction "MII1_RXD0_E14") (pintype "bidirectional"))
    )
    (net (code "220") (name "unconnected-(U1D-MII1_RXD1-PadD16)") (class "Default")
      (node (ref "U1") (pin "D16") (pinfunction "MII1_RXD1_D16") (pintype "bidirectional"))
    )
    (net (code "221") (name "unconnected-(U1D-MII1_RXD2-PadD15)") (class "Default")
      (node (ref "U1") (pin "D15") (pinfunction "MII1_RXD2_D15") (pintype "bidirectional"))
    )
    (net (code "222") (name "unconnected-(U1D-MII1_RXD3-PadD14)") (class "Default")
      (node (ref "U1") (pin "D14") (pinfunction "MII1_RXD3_D14") (pintype "bidirectional"))
    )
    (net (code "223") (name "unconnected-(U1D-MII1_RX_CLK-PadE16)") (class "Default")
      (node (ref "U1") (pin "E16") (pinfunction "MII1_RX_CLK_E16") (pintype "bidirectional"))
    )
    (net (code "224") (name "unconnected-(U1D-MII1_RX_DV-PadF16)") (class "Default")
      (node (ref "U1") (pin "F16") (pinfunction "MII1_RX_DV_F16") (pintype "bidirectional"))
    )
    (net (code "225") (name "unconnected-(U1D-MII1_RX_ER-PadE15)") (class "Default")
      (node (ref "U1") (pin "E15") (pinfunction "MII1_RX_ER_E15") (pintype "bidirectional"))
    )
    (net (code "226") (name "unconnected-(U1D-MII1_TXD0-PadH15)") (class "Default")
      (node (ref "U1") (pin "H15") (pinfunction "MII1_TXD0_H15") (pintype "bidirectional"))
    )
    (net (code "227") (name "unconnected-(U1D-MII1_TXD1-PadH14)") (class "Default")
      (node (ref "U1") (pin "H14") (pinfunction "MII1_TXD1_H14") (pintype "bidirectional"))
    )
    (net (code "228") (name "unconnected-(U1D-MII1_TXD2-PadG16)") (class "Default")
      (node (ref "U1") (pin "G16") (pinfunction "MII1_TXD2_G16") (pintype "bidirectional"))
    )
    (net (code "229") (name "unconnected-(U1D-MII1_TXD3-PadG15)") (class "Default")
      (node (ref "U1") (pin "G15") (pinfunction "MII1_TXD3_G15") (pintype "bidirectional"))
    )
    (net (code "230") (name "unconnected-(U1D-MII1_TX_CLK-PadH16)") (class "Default")
      (node (ref "U1") (pin "H16") (pinfunction "MII1_TX_CLK_H16") (pintype "bidirectional"))
    )
    (net (code "231") (name "unconnected-(U1D-MII1_TX_EN-PadG14)") (class "Default")
      (node (ref "U1") (pin "G14") (pinfunction "MII1_TX_EN_G14") (pintype "bidirectional"))
    )
    (net (code "232") (name "unconnected-(U1D-RMII1_REF_CLK-PadJ14)") (class "Default")
      (node (ref "U1") (pin "J14") (pinfunction "RMII1_REF_CLK_J14") (pintype "bidirectional"))
    )
    (net (code "233") (name "unconnected-(U1F-CAP_VDD_RTC-PadD5)") (class "Default")
      (node (ref "U1") (pin "D5") (pinfunction "CAP_VDD_RTC_D5") (pintype "bidirectional"))
    )
    (net (code "234") (name "unconnected-(U1F-NC-PadD12)") (class "Default")
      (node (ref "U1") (pin "D12") (pinfunction "NC_D12") (pintype "bidirectional"))
    )
    (net (code "235") (name "unconnected-(U1F-NC-PadJ6)") (class "Default")
      (node (ref "U1") (pin "J6") (pinfunction "NC_J6") (pintype "bidirectional"))
    )
    (net (code "236") (name "unconnected-(U1F-NC-PadK4)") (class "Default")
      (node (ref "U1") (pin "K4") (pinfunction "NC_K4") (pintype "bidirectional"))
    )
    (net (code "237") (name "unconnected-(U1F-VDDS_DDR-PadF4)") (class "Default")
      (node (ref "U1") (pin "F4") (pinfunction "VDDS_DDR_F4") (pintype "bidirectional"))
    )
    (net (code "238") (name "unconnected-(U1F-VDDS_PLL-PadG13)") (class "Default")
      (node (ref "U1") (pin "G13") (pinfunction "VDDS_PLL_G13") (pintype "bidirectional"))
    )
    (net (code "239") (name "unconnected-(U1F-VDD_CORE-PadG4)") (class "Default")
      (node (ref "U1") (pin "G4") (pinfunction "VDD_CORE_G4") (pintype "bidirectional"))
    )
    (net (code "240") (name "unconnected-(U1F-VDD_MPU-PadF13)") (class "Default")
      (node (ref "U1") (pin "F13") (pinfunction "VDD_MPU_F13") (pintype "bidirectional"))
    )
    (net (code "241") (name "unconnected-(U1F-VPP-PadH6)") (class "Default")
      (node (ref "U1") (pin "H6") (pinfunction "VPP_H6") (pintype "bidirectional"))
    )
  )
)
